# ELC102_-_Red_Digits.net
KiCad netlist of a schematic drawn in Altium Designer
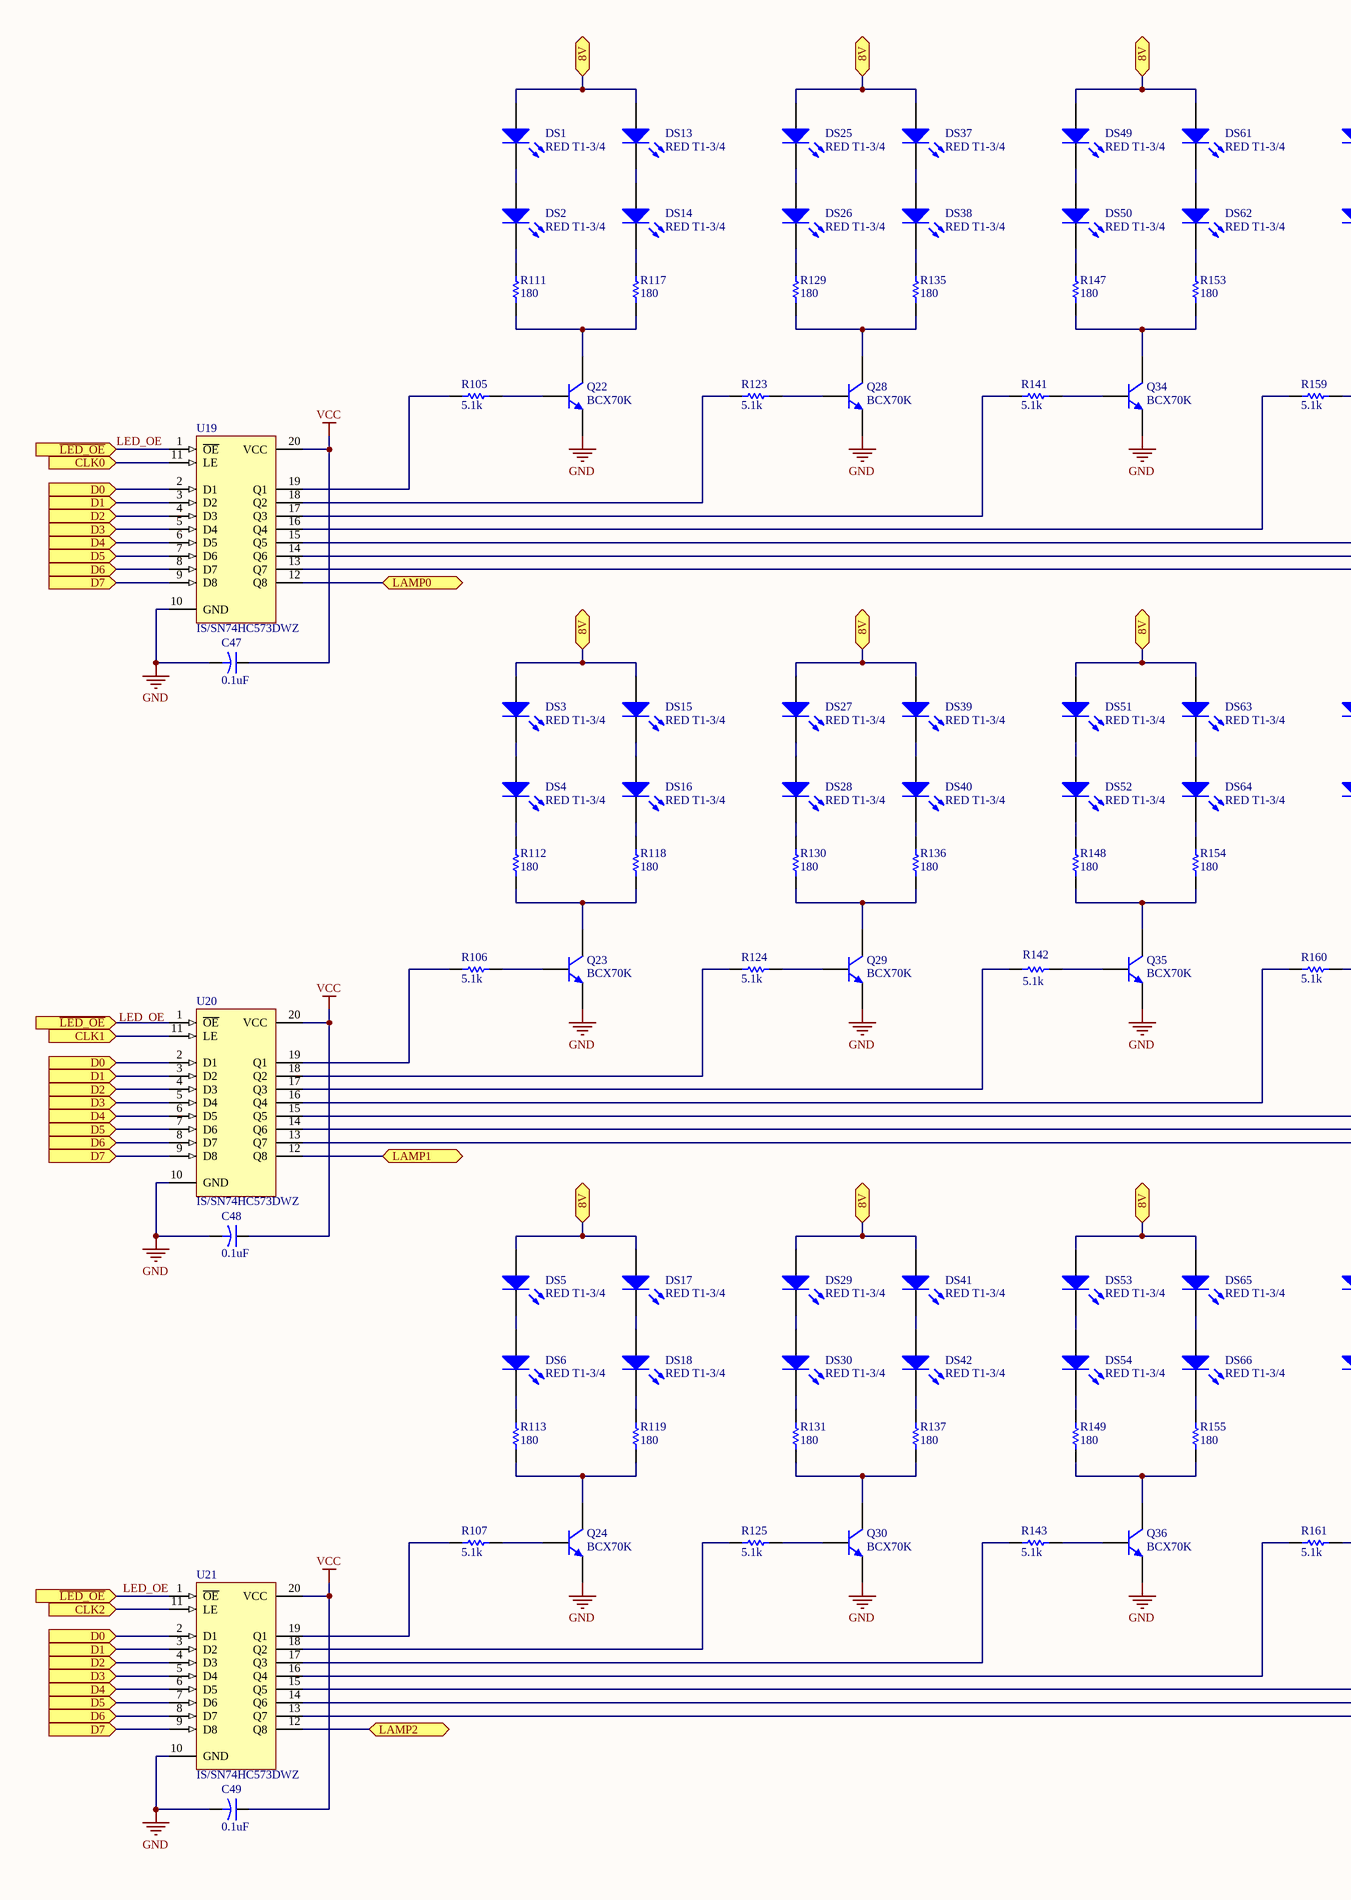
[diagram p0: ELC102 - Red Digits.SchDoc, left]
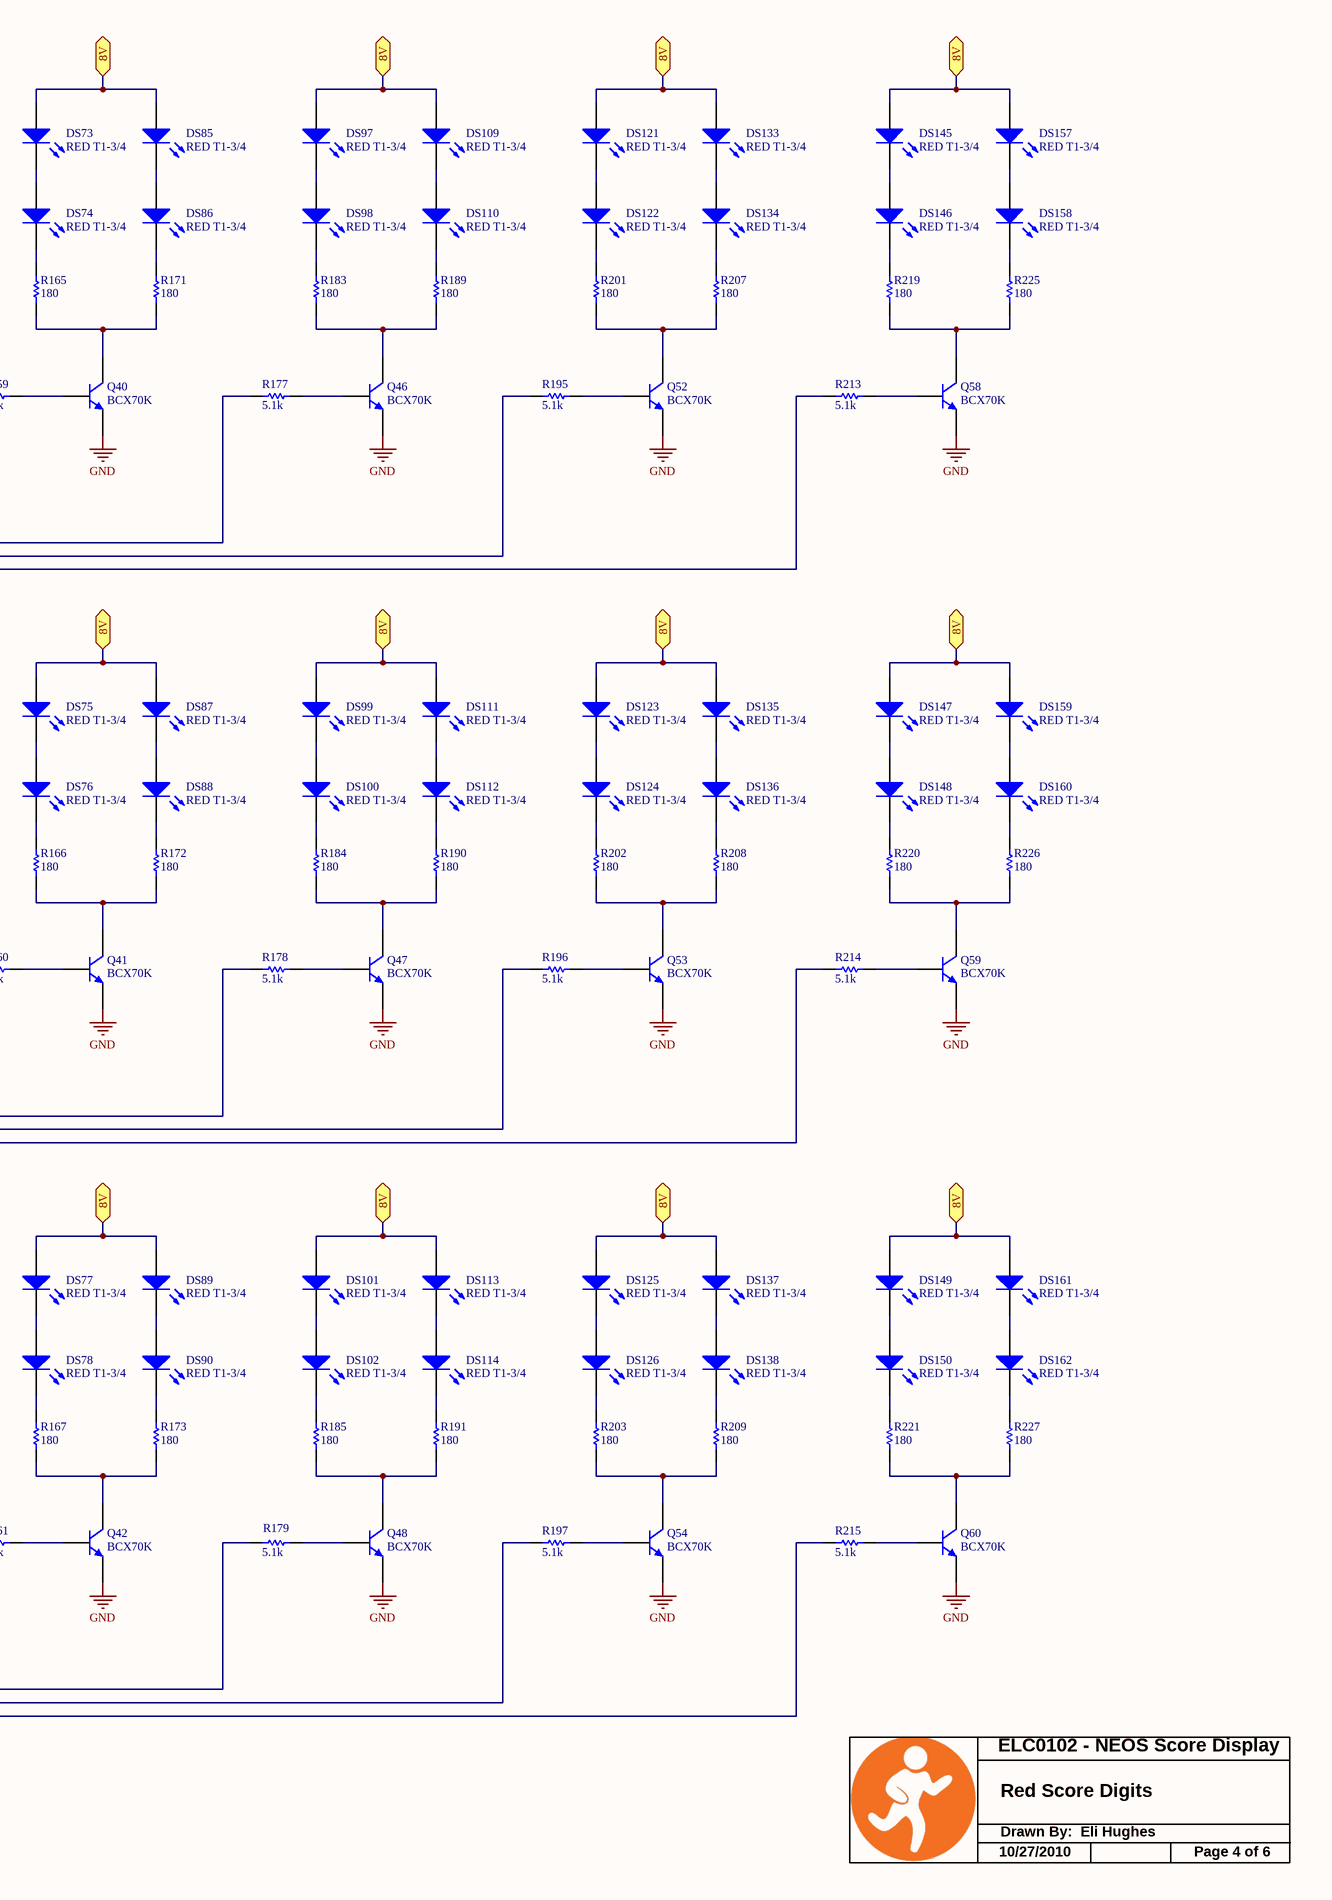
[diagram p1: ELC102 - Red Digits.SchDoc, right]

(export (version "E")
  (design (tool "Eeschema 10.0.6"))
  (components
    (comp (ref "C47")
      (value "0.1uF")
      (footprint "C0805")
      (description "CAP .10UF 50V CERAMIC X7R 0805")
      (fields
        (field (name "MANUFACTURER") "Kemet")
        (field (name "MANUFACTURER PART NUMBER") "C0805C104K5RACTU")
        (field (name "SOURCE") "Digikey")
      )
      (libsource (lib "ELC102 - Scoreboard") (part "CS/C0805C104K5RACK"))
    )
    (comp (ref "C48")
      (value "0.1uF")
      (footprint "C0805")
      (description "CAP .10UF 50V CERAMIC X7R 0805")
      (fields
        (field (name "MANUFACTURER") "Kemet")
        (field (name "MANUFACTURER PART NUMBER") "C0805C104K5RACTU")
        (field (name "SOURCE") "Digikey")
      )
      (libsource (lib "ELC102 - Scoreboard") (part "CS/C0805C104K5RACK"))
    )
    (comp (ref "C49")
      (value "0.1uF")
      (footprint "C0805")
      (description "CAP .10UF 50V CERAMIC X7R 0805")
      (fields
        (field (name "MANUFACTURER") "Kemet")
        (field (name "MANUFACTURER PART NUMBER") "C0805C104K5RACTU")
        (field (name "SOURCE") "Digikey")
      )
      (libsource (lib "ELC102 - Scoreboard") (part "CS/C0805C104K5RACK"))
    )
    (comp (ref "DS1")
      (value "RED T1-3/4")
      (footprint "LED T1-3/4 Flush")
      (description "Optek LED Red /Clear High Brightness T1-3/4")
      (fields
        (field (name "MANUFACTURER") "TT Electronics/Optek Technology")
        (field (name "MANUFACTURER PART NUMBER") "OVLFR3C7")
        (field (name "SOURCE") "Digikey")
      )
      (libsource (lib "ScoreBoard") (part "LRCOVLFR3C7Z"))
    )
    (comp (ref "DS2")
      (value "RED T1-3/4")
      (footprint "LED T1-3/4 Flush")
      (description "Optek LED Red /Clear High Brightness T1-3/4")
      (fields
        (field (name "MANUFACTURER") "TT Electronics/Optek Technology")
        (field (name "MANUFACTURER PART NUMBER") "OVLFR3C7")
        (field (name "SOURCE") "Digikey")
      )
      (libsource (lib "ScoreBoard") (part "LRCOVLFR3C7Z"))
    )
    (comp (ref "DS3")
      (value "RED T1-3/4")
      (footprint "LED T1-3/4 Flush")
      (description "Optek LED Red /Clear High Brightness T1-3/4")
      (fields
        (field (name "MANUFACTURER") "TT Electronics/Optek Technology")
        (field (name "MANUFACTURER PART NUMBER") "OVLFR3C7")
        (field (name "SOURCE") "Digikey")
      )
      (libsource (lib "ScoreBoard") (part "LRCOVLFR3C7Z"))
    )
    (comp (ref "DS4")
      (value "RED T1-3/4")
      (footprint "LED T1-3/4 Flush")
      (description "Optek LED Red /Clear High Brightness T1-3/4")
      (fields
        (field (name "MANUFACTURER") "TT Electronics/Optek Technology")
        (field (name "MANUFACTURER PART NUMBER") "OVLFR3C7")
        (field (name "SOURCE") "Digikey")
      )
      (libsource (lib "ScoreBoard") (part "LRCOVLFR3C7Z"))
    )
    (comp (ref "DS5")
      (value "RED T1-3/4")
      (footprint "LED T1-3/4 Flush")
      (description "Optek LED Red /Clear High Brightness T1-3/4")
      (fields
        (field (name "MANUFACTURER") "TT Electronics/Optek Technology")
        (field (name "MANUFACTURER PART NUMBER") "OVLFR3C7")
        (field (name "SOURCE") "Digikey")
      )
      (libsource (lib "ScoreBoard") (part "LRCOVLFR3C7Z"))
    )
    (comp (ref "DS6")
      (value "RED T1-3/4")
      (footprint "LED T1-3/4 Flush")
      (description "Optek LED Red /Clear High Brightness T1-3/4")
      (fields
        (field (name "MANUFACTURER") "TT Electronics/Optek Technology")
        (field (name "MANUFACTURER PART NUMBER") "OVLFR3C7")
        (field (name "SOURCE") "Digikey")
      )
      (libsource (lib "ScoreBoard") (part "LRCOVLFR3C7Z"))
    )
    (comp (ref "DS13")
      (value "RED T1-3/4")
      (footprint "LED T1-3/4 Flush")
      (description "Optek LED Red /Clear High Brightness T1-3/4")
      (fields
        (field (name "MANUFACTURER") "TT Electronics/Optek Technology")
        (field (name "MANUFACTURER PART NUMBER") "OVLFR3C7")
        (field (name "SOURCE") "Digikey")
      )
      (libsource (lib "ScoreBoard") (part "LRCOVLFR3C7Z"))
    )
    (comp (ref "DS14")
      (value "RED T1-3/4")
      (footprint "LED T1-3/4 Flush")
      (description "Optek LED Red /Clear High Brightness T1-3/4")
      (fields
        (field (name "MANUFACTURER") "TT Electronics/Optek Technology")
        (field (name "MANUFACTURER PART NUMBER") "OVLFR3C7")
        (field (name "SOURCE") "Digikey")
      )
      (libsource (lib "ScoreBoard") (part "LRCOVLFR3C7Z"))
    )
    (comp (ref "DS15")
      (value "RED T1-3/4")
      (footprint "LED T1-3/4 Flush")
      (description "Optek LED Red /Clear High Brightness T1-3/4")
      (fields
        (field (name "MANUFACTURER") "TT Electronics/Optek Technology")
        (field (name "MANUFACTURER PART NUMBER") "OVLFR3C7")
        (field (name "SOURCE") "Digikey")
      )
      (libsource (lib "ScoreBoard") (part "LRCOVLFR3C7Z"))
    )
    (comp (ref "DS16")
      (value "RED T1-3/4")
      (footprint "LED T1-3/4 Flush")
      (description "Optek LED Red /Clear High Brightness T1-3/4")
      (fields
        (field (name "MANUFACTURER") "TT Electronics/Optek Technology")
        (field (name "MANUFACTURER PART NUMBER") "OVLFR3C7")
        (field (name "SOURCE") "Digikey")
      )
      (libsource (lib "ScoreBoard") (part "LRCOVLFR3C7Z"))
    )
    (comp (ref "DS17")
      (value "RED T1-3/4")
      (footprint "LED T1-3/4 Flush")
      (description "Optek LED Red /Clear High Brightness T1-3/4")
      (fields
        (field (name "MANUFACTURER") "TT Electronics/Optek Technology")
        (field (name "MANUFACTURER PART NUMBER") "OVLFR3C7")
        (field (name "SOURCE") "Digikey")
      )
      (libsource (lib "ScoreBoard") (part "LRCOVLFR3C7Z"))
    )
    (comp (ref "DS18")
      (value "RED T1-3/4")
      (footprint "LED T1-3/4 Flush")
      (description "Optek LED Red /Clear High Brightness T1-3/4")
      (fields
        (field (name "MANUFACTURER") "TT Electronics/Optek Technology")
        (field (name "MANUFACTURER PART NUMBER") "OVLFR3C7")
        (field (name "SOURCE") "Digikey")
      )
      (libsource (lib "ScoreBoard") (part "LRCOVLFR3C7Z"))
    )
    (comp (ref "DS25")
      (value "RED T1-3/4")
      (footprint "LED T1-3/4 Flush")
      (description "Optek LED Red /Clear High Brightness T1-3/4")
      (fields
        (field (name "MANUFACTURER") "TT Electronics/Optek Technology")
        (field (name "MANUFACTURER PART NUMBER") "OVLFR3C7")
        (field (name "SOURCE") "Digikey")
      )
      (libsource (lib "ScoreBoard") (part "LRCOVLFR3C7Z"))
    )
    (comp (ref "DS26")
      (value "RED T1-3/4")
      (footprint "LED T1-3/4 Flush")
      (description "Optek LED Red /Clear High Brightness T1-3/4")
      (fields
        (field (name "MANUFACTURER") "TT Electronics/Optek Technology")
        (field (name "MANUFACTURER PART NUMBER") "OVLFR3C7")
        (field (name "SOURCE") "Digikey")
      )
      (libsource (lib "ScoreBoard") (part "LRCOVLFR3C7Z"))
    )
    (comp (ref "DS27")
      (value "RED T1-3/4")
      (footprint "LED T1-3/4 Flush")
      (description "Optek LED Red /Clear High Brightness T1-3/4")
      (fields
        (field (name "MANUFACTURER") "TT Electronics/Optek Technology")
        (field (name "MANUFACTURER PART NUMBER") "OVLFR3C7")
        (field (name "SOURCE") "Digikey")
      )
      (libsource (lib "ScoreBoard") (part "LRCOVLFR3C7Z"))
    )
    (comp (ref "DS28")
      (value "RED T1-3/4")
      (footprint "LED T1-3/4 Flush")
      (description "Optek LED Red /Clear High Brightness T1-3/4")
      (fields
        (field (name "MANUFACTURER") "TT Electronics/Optek Technology")
        (field (name "MANUFACTURER PART NUMBER") "OVLFR3C7")
        (field (name "SOURCE") "Digikey")
      )
      (libsource (lib "ScoreBoard") (part "LRCOVLFR3C7Z"))
    )
    (comp (ref "DS29")
      (value "RED T1-3/4")
      (footprint "LED T1-3/4 Flush")
      (description "Optek LED Red /Clear High Brightness T1-3/4")
      (fields
        (field (name "MANUFACTURER") "TT Electronics/Optek Technology")
        (field (name "MANUFACTURER PART NUMBER") "OVLFR3C7")
        (field (name "SOURCE") "Digikey")
      )
      (libsource (lib "ScoreBoard") (part "LRCOVLFR3C7Z"))
    )
    (comp (ref "DS30")
      (value "RED T1-3/4")
      (footprint "LED T1-3/4 Flush")
      (description "Optek LED Red /Clear High Brightness T1-3/4")
      (fields
        (field (name "MANUFACTURER") "TT Electronics/Optek Technology")
        (field (name "MANUFACTURER PART NUMBER") "OVLFR3C7")
        (field (name "SOURCE") "Digikey")
      )
      (libsource (lib "ScoreBoard") (part "LRCOVLFR3C7Z"))
    )
    (comp (ref "DS37")
      (value "RED T1-3/4")
      (footprint "LED T1-3/4 Flush")
      (description "Optek LED Red /Clear High Brightness T1-3/4")
      (fields
        (field (name "MANUFACTURER") "TT Electronics/Optek Technology")
        (field (name "MANUFACTURER PART NUMBER") "OVLFR3C7")
        (field (name "SOURCE") "Digikey")
      )
      (libsource (lib "ScoreBoard") (part "LRCOVLFR3C7Z"))
    )
    (comp (ref "DS38")
      (value "RED T1-3/4")
      (footprint "LED T1-3/4 Flush")
      (description "Optek LED Red /Clear High Brightness T1-3/4")
      (fields
        (field (name "MANUFACTURER") "TT Electronics/Optek Technology")
        (field (name "MANUFACTURER PART NUMBER") "OVLFR3C7")
        (field (name "SOURCE") "Digikey")
      )
      (libsource (lib "ScoreBoard") (part "LRCOVLFR3C7Z"))
    )
    (comp (ref "DS39")
      (value "RED T1-3/4")
      (footprint "LED T1-3/4 Flush")
      (description "Optek LED Red /Clear High Brightness T1-3/4")
      (fields
        (field (name "MANUFACTURER") "TT Electronics/Optek Technology")
        (field (name "MANUFACTURER PART NUMBER") "OVLFR3C7")
        (field (name "SOURCE") "Digikey")
      )
      (libsource (lib "ScoreBoard") (part "LRCOVLFR3C7Z"))
    )
    (comp (ref "DS40")
      (value "RED T1-3/4")
      (footprint "LED T1-3/4 Flush")
      (description "Optek LED Red /Clear High Brightness T1-3/4")
      (fields
        (field (name "MANUFACTURER") "TT Electronics/Optek Technology")
        (field (name "MANUFACTURER PART NUMBER") "OVLFR3C7")
        (field (name "SOURCE") "Digikey")
      )
      (libsource (lib "ScoreBoard") (part "LRCOVLFR3C7Z"))
    )
    (comp (ref "DS41")
      (value "RED T1-3/4")
      (footprint "LED T1-3/4 Flush")
      (description "Optek LED Red /Clear High Brightness T1-3/4")
      (fields
        (field (name "MANUFACTURER") "TT Electronics/Optek Technology")
        (field (name "MANUFACTURER PART NUMBER") "OVLFR3C7")
        (field (name "SOURCE") "Digikey")
      )
      (libsource (lib "ScoreBoard") (part "LRCOVLFR3C7Z"))
    )
    (comp (ref "DS42")
      (value "RED T1-3/4")
      (footprint "LED T1-3/4 Flush")
      (description "Optek LED Red /Clear High Brightness T1-3/4")
      (fields
        (field (name "MANUFACTURER") "TT Electronics/Optek Technology")
        (field (name "MANUFACTURER PART NUMBER") "OVLFR3C7")
        (field (name "SOURCE") "Digikey")
      )
      (libsource (lib "ScoreBoard") (part "LRCOVLFR3C7Z"))
    )
    (comp (ref "DS49")
      (value "RED T1-3/4")
      (footprint "LED T1-3/4 Flush")
      (description "Optek LED Red /Clear High Brightness T1-3/4")
      (fields
        (field (name "MANUFACTURER") "TT Electronics/Optek Technology")
        (field (name "MANUFACTURER PART NUMBER") "OVLFR3C7")
        (field (name "SOURCE") "Digikey")
      )
      (libsource (lib "ScoreBoard") (part "LRCOVLFR3C7Z"))
    )
    (comp (ref "DS50")
      (value "RED T1-3/4")
      (footprint "LED T1-3/4 Flush")
      (description "Optek LED Red /Clear High Brightness T1-3/4")
      (fields
        (field (name "MANUFACTURER") "TT Electronics/Optek Technology")
        (field (name "MANUFACTURER PART NUMBER") "OVLFR3C7")
        (field (name "SOURCE") "Digikey")
      )
      (libsource (lib "ScoreBoard") (part "LRCOVLFR3C7Z"))
    )
    (comp (ref "DS51")
      (value "RED T1-3/4")
      (footprint "LED T1-3/4 Flush")
      (description "Optek LED Red /Clear High Brightness T1-3/4")
      (fields
        (field (name "MANUFACTURER") "TT Electronics/Optek Technology")
        (field (name "MANUFACTURER PART NUMBER") "OVLFR3C7")
        (field (name "SOURCE") "Digikey")
      )
      (libsource (lib "ScoreBoard") (part "LRCOVLFR3C7Z"))
    )
    (comp (ref "DS52")
      (value "RED T1-3/4")
      (footprint "LED T1-3/4 Flush")
      (description "Optek LED Red /Clear High Brightness T1-3/4")
      (fields
        (field (name "MANUFACTURER") "TT Electronics/Optek Technology")
        (field (name "MANUFACTURER PART NUMBER") "OVLFR3C7")
        (field (name "SOURCE") "Digikey")
      )
      (libsource (lib "ScoreBoard") (part "LRCOVLFR3C7Z"))
    )
    (comp (ref "DS53")
      (value "RED T1-3/4")
      (footprint "LED T1-3/4 Flush")
      (description "Optek LED Red /Clear High Brightness T1-3/4")
      (fields
        (field (name "MANUFACTURER") "TT Electronics/Optek Technology")
        (field (name "MANUFACTURER PART NUMBER") "OVLFR3C7")
        (field (name "SOURCE") "Digikey")
      )
      (libsource (lib "ScoreBoard") (part "LRCOVLFR3C7Z"))
    )
    (comp (ref "DS54")
      (value "RED T1-3/4")
      (footprint "LED T1-3/4 Flush")
      (description "Optek LED Red /Clear High Brightness T1-3/4")
      (fields
        (field (name "MANUFACTURER") "TT Electronics/Optek Technology")
        (field (name "MANUFACTURER PART NUMBER") "OVLFR3C7")
        (field (name "SOURCE") "Digikey")
      )
      (libsource (lib "ScoreBoard") (part "LRCOVLFR3C7Z"))
    )
    (comp (ref "DS61")
      (value "RED T1-3/4")
      (footprint "LED T1-3/4 Flush")
      (description "Optek LED Red /Clear High Brightness T1-3/4")
      (fields
        (field (name "MANUFACTURER") "TT Electronics/Optek Technology")
        (field (name "MANUFACTURER PART NUMBER") "OVLFR3C7")
        (field (name "SOURCE") "Digikey")
      )
      (libsource (lib "ScoreBoard") (part "LRCOVLFR3C7Z"))
    )
    (comp (ref "DS62")
      (value "RED T1-3/4")
      (footprint "LED T1-3/4 Flush")
      (description "Optek LED Red /Clear High Brightness T1-3/4")
      (fields
        (field (name "MANUFACTURER") "TT Electronics/Optek Technology")
        (field (name "MANUFACTURER PART NUMBER") "OVLFR3C7")
        (field (name "SOURCE") "Digikey")
      )
      (libsource (lib "ScoreBoard") (part "LRCOVLFR3C7Z"))
    )
    (comp (ref "DS63")
      (value "RED T1-3/4")
      (footprint "LED T1-3/4 Flush")
      (description "Optek LED Red /Clear High Brightness T1-3/4")
      (fields
        (field (name "MANUFACTURER") "TT Electronics/Optek Technology")
        (field (name "MANUFACTURER PART NUMBER") "OVLFR3C7")
        (field (name "SOURCE") "Digikey")
      )
      (libsource (lib "ScoreBoard") (part "LRCOVLFR3C7Z"))
    )
    (comp (ref "DS64")
      (value "RED T1-3/4")
      (footprint "LED T1-3/4 Flush")
      (description "Optek LED Red /Clear High Brightness T1-3/4")
      (fields
        (field (name "MANUFACTURER") "TT Electronics/Optek Technology")
        (field (name "MANUFACTURER PART NUMBER") "OVLFR3C7")
        (field (name "SOURCE") "Digikey")
      )
      (libsource (lib "ScoreBoard") (part "LRCOVLFR3C7Z"))
    )
    (comp (ref "DS65")
      (value "RED T1-3/4")
      (footprint "LED T1-3/4 Flush")
      (description "Optek LED Red /Clear High Brightness T1-3/4")
      (fields
        (field (name "MANUFACTURER") "TT Electronics/Optek Technology")
        (field (name "MANUFACTURER PART NUMBER") "OVLFR3C7")
        (field (name "SOURCE") "Digikey")
      )
      (libsource (lib "ScoreBoard") (part "LRCOVLFR3C7Z"))
    )
    (comp (ref "DS66")
      (value "RED T1-3/4")
      (footprint "LED T1-3/4 Flush")
      (description "Optek LED Red /Clear High Brightness T1-3/4")
      (fields
        (field (name "MANUFACTURER") "TT Electronics/Optek Technology")
        (field (name "MANUFACTURER PART NUMBER") "OVLFR3C7")
        (field (name "SOURCE") "Digikey")
      )
      (libsource (lib "ScoreBoard") (part "LRCOVLFR3C7Z"))
    )
    (comp (ref "DS73")
      (value "RED T1-3/4")
      (footprint "LED T1-3/4 Flush")
      (description "Optek LED Red /Clear High Brightness T1-3/4")
      (fields
        (field (name "MANUFACTURER") "TT Electronics/Optek Technology")
        (field (name "MANUFACTURER PART NUMBER") "OVLFR3C7")
        (field (name "SOURCE") "Digikey")
      )
      (libsource (lib "ScoreBoard") (part "LRCOVLFR3C7Z"))
    )
    (comp (ref "DS74")
      (value "RED T1-3/4")
      (footprint "LED T1-3/4 Flush")
      (description "Optek LED Red /Clear High Brightness T1-3/4")
      (fields
        (field (name "MANUFACTURER") "TT Electronics/Optek Technology")
        (field (name "MANUFACTURER PART NUMBER") "OVLFR3C7")
        (field (name "SOURCE") "Digikey")
      )
      (libsource (lib "ScoreBoard") (part "LRCOVLFR3C7Z"))
    )
    (comp (ref "DS75")
      (value "RED T1-3/4")
      (footprint "LED T1-3/4 Flush")
      (description "Optek LED Red /Clear High Brightness T1-3/4")
      (fields
        (field (name "MANUFACTURER") "TT Electronics/Optek Technology")
        (field (name "MANUFACTURER PART NUMBER") "OVLFR3C7")
        (field (name "SOURCE") "Digikey")
      )
      (libsource (lib "ScoreBoard") (part "LRCOVLFR3C7Z"))
    )
    (comp (ref "DS76")
      (value "RED T1-3/4")
      (footprint "LED T1-3/4 Flush")
      (description "Optek LED Red /Clear High Brightness T1-3/4")
      (fields
        (field (name "MANUFACTURER") "TT Electronics/Optek Technology")
        (field (name "MANUFACTURER PART NUMBER") "OVLFR3C7")
        (field (name "SOURCE") "Digikey")
      )
      (libsource (lib "ScoreBoard") (part "LRCOVLFR3C7Z"))
    )
    (comp (ref "DS77")
      (value "RED T1-3/4")
      (footprint "LED T1-3/4 Flush")
      (description "Optek LED Red /Clear High Brightness T1-3/4")
      (fields
        (field (name "MANUFACTURER") "TT Electronics/Optek Technology")
        (field (name "MANUFACTURER PART NUMBER") "OVLFR3C7")
        (field (name "SOURCE") "Digikey")
      )
      (libsource (lib "ScoreBoard") (part "LRCOVLFR3C7Z"))
    )
    (comp (ref "DS78")
      (value "RED T1-3/4")
      (footprint "LED T1-3/4 Flush")
      (description "Optek LED Red /Clear High Brightness T1-3/4")
      (fields
        (field (name "MANUFACTURER") "TT Electronics/Optek Technology")
        (field (name "MANUFACTURER PART NUMBER") "OVLFR3C7")
        (field (name "SOURCE") "Digikey")
      )
      (libsource (lib "ScoreBoard") (part "LRCOVLFR3C7Z"))
    )
    (comp (ref "DS85")
      (value "RED T1-3/4")
      (footprint "LED T1-3/4 Flush")
      (description "Optek LED Red /Clear High Brightness T1-3/4")
      (fields
        (field (name "MANUFACTURER") "TT Electronics/Optek Technology")
        (field (name "MANUFACTURER PART NUMBER") "OVLFR3C7")
        (field (name "SOURCE") "Digikey")
      )
      (libsource (lib "ScoreBoard") (part "LRCOVLFR3C7Z"))
    )
    (comp (ref "DS86")
      (value "RED T1-3/4")
      (footprint "LED T1-3/4 Flush")
      (description "Optek LED Red /Clear High Brightness T1-3/4")
      (fields
        (field (name "MANUFACTURER") "TT Electronics/Optek Technology")
        (field (name "MANUFACTURER PART NUMBER") "OVLFR3C7")
        (field (name "SOURCE") "Digikey")
      )
      (libsource (lib "ScoreBoard") (part "LRCOVLFR3C7Z"))
    )
    (comp (ref "DS87")
      (value "RED T1-3/4")
      (footprint "LED T1-3/4 Flush")
      (description "Optek LED Red /Clear High Brightness T1-3/4")
      (fields
        (field (name "MANUFACTURER") "TT Electronics/Optek Technology")
        (field (name "MANUFACTURER PART NUMBER") "OVLFR3C7")
        (field (name "SOURCE") "Digikey")
      )
      (libsource (lib "ScoreBoard") (part "LRCOVLFR3C7Z"))
    )
    (comp (ref "DS88")
      (value "RED T1-3/4")
      (footprint "LED T1-3/4 Flush")
      (description "Optek LED Red /Clear High Brightness T1-3/4")
      (fields
        (field (name "MANUFACTURER") "TT Electronics/Optek Technology")
        (field (name "MANUFACTURER PART NUMBER") "OVLFR3C7")
        (field (name "SOURCE") "Digikey")
      )
      (libsource (lib "ScoreBoard") (part "LRCOVLFR3C7Z"))
    )
    (comp (ref "DS89")
      (value "RED T1-3/4")
      (footprint "LED T1-3/4 Flush")
      (description "Optek LED Red /Clear High Brightness T1-3/4")
      (fields
        (field (name "MANUFACTURER") "TT Electronics/Optek Technology")
        (field (name "MANUFACTURER PART NUMBER") "OVLFR3C7")
        (field (name "SOURCE") "Digikey")
      )
      (libsource (lib "ScoreBoard") (part "LRCOVLFR3C7Z"))
    )
    (comp (ref "DS90")
      (value "RED T1-3/4")
      (footprint "LED T1-3/4 Flush")
      (description "Optek LED Red /Clear High Brightness T1-3/4")
      (fields
        (field (name "MANUFACTURER") "TT Electronics/Optek Technology")
        (field (name "MANUFACTURER PART NUMBER") "OVLFR3C7")
        (field (name "SOURCE") "Digikey")
      )
      (libsource (lib "ScoreBoard") (part "LRCOVLFR3C7Z"))
    )
    (comp (ref "DS97")
      (value "RED T1-3/4")
      (footprint "LED T1-3/4 Flush")
      (description "Optek LED Red /Clear High Brightness T1-3/4")
      (fields
        (field (name "MANUFACTURER") "TT Electronics/Optek Technology")
        (field (name "MANUFACTURER PART NUMBER") "OVLFR3C7")
        (field (name "SOURCE") "Digikey")
      )
      (libsource (lib "ScoreBoard") (part "LRCOVLFR3C7Z"))
    )
    (comp (ref "DS98")
      (value "RED T1-3/4")
      (footprint "LED T1-3/4 Flush")
      (description "Optek LED Red /Clear High Brightness T1-3/4")
      (fields
        (field (name "MANUFACTURER") "TT Electronics/Optek Technology")
        (field (name "MANUFACTURER PART NUMBER") "OVLFR3C7")
        (field (name "SOURCE") "Digikey")
      )
      (libsource (lib "ScoreBoard") (part "LRCOVLFR3C7Z"))
    )
    (comp (ref "DS99")
      (value "RED T1-3/4")
      (footprint "LED T1-3/4 Flush")
      (description "Optek LED Red /Clear High Brightness T1-3/4")
      (fields
        (field (name "MANUFACTURER") "TT Electronics/Optek Technology")
        (field (name "MANUFACTURER PART NUMBER") "OVLFR3C7")
        (field (name "SOURCE") "Digikey")
      )
      (libsource (lib "ScoreBoard") (part "LRCOVLFR3C7Z"))
    )
    (comp (ref "DS100")
      (value "RED T1-3/4")
      (footprint "LED T1-3/4 Flush")
      (description "Optek LED Red /Clear High Brightness T1-3/4")
      (fields
        (field (name "MANUFACTURER") "TT Electronics/Optek Technology")
        (field (name "MANUFACTURER PART NUMBER") "OVLFR3C7")
        (field (name "SOURCE") "Digikey")
      )
      (libsource (lib "ScoreBoard") (part "LRCOVLFR3C7Z"))
    )
    (comp (ref "DS101")
      (value "RED T1-3/4")
      (footprint "LED T1-3/4 Flush")
      (description "Optek LED Red /Clear High Brightness T1-3/4")
      (fields
        (field (name "MANUFACTURER") "TT Electronics/Optek Technology")
        (field (name "MANUFACTURER PART NUMBER") "OVLFR3C7")
        (field (name "SOURCE") "Digikey")
      )
      (libsource (lib "ScoreBoard") (part "LRCOVLFR3C7Z"))
    )
    (comp (ref "DS102")
      (value "RED T1-3/4")
      (footprint "LED T1-3/4 Flush")
      (description "Optek LED Red /Clear High Brightness T1-3/4")
      (fields
        (field (name "MANUFACTURER") "TT Electronics/Optek Technology")
        (field (name "MANUFACTURER PART NUMBER") "OVLFR3C7")
        (field (name "SOURCE") "Digikey")
      )
      (libsource (lib "ScoreBoard") (part "LRCOVLFR3C7Z"))
    )
    (comp (ref "DS109")
      (value "RED T1-3/4")
      (footprint "LED T1-3/4 Flush")
      (description "Optek LED Red /Clear High Brightness T1-3/4")
      (fields
        (field (name "MANUFACTURER") "TT Electronics/Optek Technology")
        (field (name "MANUFACTURER PART NUMBER") "OVLFR3C7")
        (field (name "SOURCE") "Digikey")
      )
      (libsource (lib "ScoreBoard") (part "LRCOVLFR3C7Z"))
    )
    (comp (ref "DS110")
      (value "RED T1-3/4")
      (footprint "LED T1-3/4 Flush")
      (description "Optek LED Red /Clear High Brightness T1-3/4")
      (fields
        (field (name "MANUFACTURER") "TT Electronics/Optek Technology")
        (field (name "MANUFACTURER PART NUMBER") "OVLFR3C7")
        (field (name "SOURCE") "Digikey")
      )
      (libsource (lib "ScoreBoard") (part "LRCOVLFR3C7Z"))
    )
    (comp (ref "DS111")
      (value "RED T1-3/4")
      (footprint "LED T1-3/4 Flush")
      (description "Optek LED Red /Clear High Brightness T1-3/4")
      (fields
        (field (name "MANUFACTURER") "TT Electronics/Optek Technology")
        (field (name "MANUFACTURER PART NUMBER") "OVLFR3C7")
        (field (name "SOURCE") "Digikey")
      )
      (libsource (lib "ScoreBoard") (part "LRCOVLFR3C7Z"))
    )
    (comp (ref "DS112")
      (value "RED T1-3/4")
      (footprint "LED T1-3/4 Flush")
      (description "Optek LED Red /Clear High Brightness T1-3/4")
      (fields
        (field (name "MANUFACTURER") "TT Electronics/Optek Technology")
        (field (name "MANUFACTURER PART NUMBER") "OVLFR3C7")
        (field (name "SOURCE") "Digikey")
      )
      (libsource (lib "ScoreBoard") (part "LRCOVLFR3C7Z"))
    )
    (comp (ref "DS113")
      (value "RED T1-3/4")
      (footprint "LED T1-3/4 Flush")
      (description "Optek LED Red /Clear High Brightness T1-3/4")
      (fields
        (field (name "MANUFACTURER") "TT Electronics/Optek Technology")
        (field (name "MANUFACTURER PART NUMBER") "OVLFR3C7")
        (field (name "SOURCE") "Digikey")
      )
      (libsource (lib "ScoreBoard") (part "LRCOVLFR3C7Z"))
    )
    (comp (ref "DS114")
      (value "RED T1-3/4")
      (footprint "LED T1-3/4 Flush")
      (description "Optek LED Red /Clear High Brightness T1-3/4")
      (fields
        (field (name "MANUFACTURER") "TT Electronics/Optek Technology")
        (field (name "MANUFACTURER PART NUMBER") "OVLFR3C7")
        (field (name "SOURCE") "Digikey")
      )
      (libsource (lib "ScoreBoard") (part "LRCOVLFR3C7Z"))
    )
    (comp (ref "DS121")
      (value "RED T1-3/4")
      (footprint "LED T1-3/4 Flush")
      (description "Optek LED Red /Clear High Brightness T1-3/4")
      (fields
        (field (name "MANUFACTURER") "TT Electronics/Optek Technology")
        (field (name "MANUFACTURER PART NUMBER") "OVLFR3C7")
        (field (name "SOURCE") "Digikey")
      )
      (libsource (lib "ScoreBoard") (part "LRCOVLFR3C7Z"))
    )
    (comp (ref "DS122")
      (value "RED T1-3/4")
      (footprint "LED T1-3/4 Flush")
      (description "Optek LED Red /Clear High Brightness T1-3/4")
      (fields
        (field (name "MANUFACTURER") "TT Electronics/Optek Technology")
        (field (name "MANUFACTURER PART NUMBER") "OVLFR3C7")
        (field (name "SOURCE") "Digikey")
      )
      (libsource (lib "ScoreBoard") (part "LRCOVLFR3C7Z"))
    )
    (comp (ref "DS123")
      (value "RED T1-3/4")
      (footprint "LED T1-3/4 Flush")
      (description "Optek LED Red /Clear High Brightness T1-3/4")
      (fields
        (field (name "MANUFACTURER") "TT Electronics/Optek Technology")
        (field (name "MANUFACTURER PART NUMBER") "OVLFR3C7")
        (field (name "SOURCE") "Digikey")
      )
      (libsource (lib "ScoreBoard") (part "LRCOVLFR3C7Z"))
    )
    (comp (ref "DS124")
      (value "RED T1-3/4")
      (footprint "LED T1-3/4 Flush")
      (description "Optek LED Red /Clear High Brightness T1-3/4")
      (fields
        (field (name "MANUFACTURER") "TT Electronics/Optek Technology")
        (field (name "MANUFACTURER PART NUMBER") "OVLFR3C7")
        (field (name "SOURCE") "Digikey")
      )
      (libsource (lib "ScoreBoard") (part "LRCOVLFR3C7Z"))
    )
    (comp (ref "DS125")
      (value "RED T1-3/4")
      (footprint "LED T1-3/4 Flush")
      (description "Optek LED Red /Clear High Brightness T1-3/4")
      (fields
        (field (name "MANUFACTURER") "TT Electronics/Optek Technology")
        (field (name "MANUFACTURER PART NUMBER") "OVLFR3C7")
        (field (name "SOURCE") "Digikey")
      )
      (libsource (lib "ScoreBoard") (part "LRCOVLFR3C7Z"))
    )
    (comp (ref "DS126")
      (value "RED T1-3/4")
      (footprint "LED T1-3/4 Flush")
      (description "Optek LED Red /Clear High Brightness T1-3/4")
      (fields
        (field (name "MANUFACTURER") "TT Electronics/Optek Technology")
        (field (name "MANUFACTURER PART NUMBER") "OVLFR3C7")
        (field (name "SOURCE") "Digikey")
      )
      (libsource (lib "ScoreBoard") (part "LRCOVLFR3C7Z"))
    )
    (comp (ref "DS133")
      (value "RED T1-3/4")
      (footprint "LED T1-3/4 Flush")
      (description "Optek LED Red /Clear High Brightness T1-3/4")
      (fields
        (field (name "MANUFACTURER") "TT Electronics/Optek Technology")
        (field (name "MANUFACTURER PART NUMBER") "OVLFR3C7")
        (field (name "SOURCE") "Digikey")
      )
      (libsource (lib "ScoreBoard") (part "LRCOVLFR3C7Z"))
    )
    (comp (ref "DS134")
      (value "RED T1-3/4")
      (footprint "LED T1-3/4 Flush")
      (description "Optek LED Red /Clear High Brightness T1-3/4")
      (fields
        (field (name "MANUFACTURER") "TT Electronics/Optek Technology")
        (field (name "MANUFACTURER PART NUMBER") "OVLFR3C7")
        (field (name "SOURCE") "Digikey")
      )
      (libsource (lib "ScoreBoard") (part "LRCOVLFR3C7Z"))
    )
    (comp (ref "DS135")
      (value "RED T1-3/4")
      (footprint "LED T1-3/4 Flush")
      (description "Optek LED Red /Clear High Brightness T1-3/4")
      (fields
        (field (name "MANUFACTURER") "TT Electronics/Optek Technology")
        (field (name "MANUFACTURER PART NUMBER") "OVLFR3C7")
        (field (name "SOURCE") "Digikey")
      )
      (libsource (lib "ScoreBoard") (part "LRCOVLFR3C7Z"))
    )
    (comp (ref "DS136")
      (value "RED T1-3/4")
      (footprint "LED T1-3/4 Flush")
      (description "Optek LED Red /Clear High Brightness T1-3/4")
      (fields
        (field (name "MANUFACTURER") "TT Electronics/Optek Technology")
        (field (name "MANUFACTURER PART NUMBER") "OVLFR3C7")
        (field (name "SOURCE") "Digikey")
      )
      (libsource (lib "ScoreBoard") (part "LRCOVLFR3C7Z"))
    )
    (comp (ref "DS137")
      (value "RED T1-3/4")
      (footprint "LED T1-3/4 Flush")
      (description "Optek LED Red /Clear High Brightness T1-3/4")
      (fields
        (field (name "MANUFACTURER") "TT Electronics/Optek Technology")
        (field (name "MANUFACTURER PART NUMBER") "OVLFR3C7")
        (field (name "SOURCE") "Digikey")
      )
      (libsource (lib "ScoreBoard") (part "LRCOVLFR3C7Z"))
    )
    (comp (ref "DS138")
      (value "RED T1-3/4")
      (footprint "LED T1-3/4 Flush")
      (description "Optek LED Red /Clear High Brightness T1-3/4")
      (fields
        (field (name "MANUFACTURER") "TT Electronics/Optek Technology")
        (field (name "MANUFACTURER PART NUMBER") "OVLFR3C7")
        (field (name "SOURCE") "Digikey")
      )
      (libsource (lib "ScoreBoard") (part "LRCOVLFR3C7Z"))
    )
    (comp (ref "DS145")
      (value "RED T1-3/4")
      (footprint "LED T1-3/4 Flush")
      (description "Optek LED Red /Clear High Brightness T1-3/4")
      (fields
        (field (name "MANUFACTURER") "TT Electronics/Optek Technology")
        (field (name "MANUFACTURER PART NUMBER") "OVLFR3C7")
        (field (name "SOURCE") "Digikey")
      )
      (libsource (lib "ScoreBoard") (part "LRCOVLFR3C7Z"))
    )
    (comp (ref "DS146")
      (value "RED T1-3/4")
      (footprint "LED T1-3/4 Flush")
      (description "Optek LED Red /Clear High Brightness T1-3/4")
      (fields
        (field (name "MANUFACTURER") "TT Electronics/Optek Technology")
        (field (name "MANUFACTURER PART NUMBER") "OVLFR3C7")
        (field (name "SOURCE") "Digikey")
      )
      (libsource (lib "ScoreBoard") (part "LRCOVLFR3C7Z"))
    )
    (comp (ref "DS147")
      (value "RED T1-3/4")
      (footprint "LED T1-3/4 Flush")
      (description "Optek LED Red /Clear High Brightness T1-3/4")
      (fields
        (field (name "MANUFACTURER") "TT Electronics/Optek Technology")
        (field (name "MANUFACTURER PART NUMBER") "OVLFR3C7")
        (field (name "SOURCE") "Digikey")
      )
      (libsource (lib "ScoreBoard") (part "LRCOVLFR3C7Z"))
    )
    (comp (ref "DS148")
      (value "RED T1-3/4")
      (footprint "LED T1-3/4 Flush")
      (description "Optek LED Red /Clear High Brightness T1-3/4")
      (fields
        (field (name "MANUFACTURER") "TT Electronics/Optek Technology")
        (field (name "MANUFACTURER PART NUMBER") "OVLFR3C7")
        (field (name "SOURCE") "Digikey")
      )
      (libsource (lib "ScoreBoard") (part "LRCOVLFR3C7Z"))
    )
    (comp (ref "DS149")
      (value "RED T1-3/4")
      (footprint "LED T1-3/4 Flush")
      (description "Optek LED Red /Clear High Brightness T1-3/4")
      (fields
        (field (name "MANUFACTURER") "TT Electronics/Optek Technology")
        (field (name "MANUFACTURER PART NUMBER") "OVLFR3C7")
        (field (name "SOURCE") "Digikey")
      )
      (libsource (lib "ScoreBoard") (part "LRCOVLFR3C7Z"))
    )
    (comp (ref "DS150")
      (value "RED T1-3/4")
      (footprint "LED T1-3/4 Flush")
      (description "Optek LED Red /Clear High Brightness T1-3/4")
      (fields
        (field (name "MANUFACTURER") "TT Electronics/Optek Technology")
        (field (name "MANUFACTURER PART NUMBER") "OVLFR3C7")
        (field (name "SOURCE") "Digikey")
      )
      (libsource (lib "ScoreBoard") (part "LRCOVLFR3C7Z"))
    )
    (comp (ref "DS157")
      (value "RED T1-3/4")
      (footprint "LED T1-3/4 Flush")
      (description "Optek LED Red /Clear High Brightness T1-3/4")
      (fields
        (field (name "MANUFACTURER") "TT Electronics/Optek Technology")
        (field (name "MANUFACTURER PART NUMBER") "OVLFR3C7")
        (field (name "SOURCE") "Digikey")
      )
      (libsource (lib "ScoreBoard") (part "LRCOVLFR3C7Z"))
    )
    (comp (ref "DS158")
      (value "RED T1-3/4")
      (footprint "LED T1-3/4 Flush")
      (description "Optek LED Red /Clear High Brightness T1-3/4")
      (fields
        (field (name "MANUFACTURER") "TT Electronics/Optek Technology")
        (field (name "MANUFACTURER PART NUMBER") "OVLFR3C7")
        (field (name "SOURCE") "Digikey")
      )
      (libsource (lib "ScoreBoard") (part "LRCOVLFR3C7Z"))
    )
    (comp (ref "DS159")
      (value "RED T1-3/4")
      (footprint "LED T1-3/4 Flush")
      (description "Optek LED Red /Clear High Brightness T1-3/4")
      (fields
        (field (name "MANUFACTURER") "TT Electronics/Optek Technology")
        (field (name "MANUFACTURER PART NUMBER") "OVLFR3C7")
        (field (name "SOURCE") "Digikey")
      )
      (libsource (lib "ScoreBoard") (part "LRCOVLFR3C7Z"))
    )
    (comp (ref "DS160")
      (value "RED T1-3/4")
      (footprint "LED T1-3/4 Flush")
      (description "Optek LED Red /Clear High Brightness T1-3/4")
      (fields
        (field (name "MANUFACTURER") "TT Electronics/Optek Technology")
        (field (name "MANUFACTURER PART NUMBER") "OVLFR3C7")
        (field (name "SOURCE") "Digikey")
      )
      (libsource (lib "ScoreBoard") (part "LRCOVLFR3C7Z"))
    )
    (comp (ref "DS161")
      (value "RED T1-3/4")
      (footprint "LED T1-3/4 Flush")
      (description "Optek LED Red /Clear High Brightness T1-3/4")
      (fields
        (field (name "MANUFACTURER") "TT Electronics/Optek Technology")
        (field (name "MANUFACTURER PART NUMBER") "OVLFR3C7")
        (field (name "SOURCE") "Digikey")
      )
      (libsource (lib "ScoreBoard") (part "LRCOVLFR3C7Z"))
    )
    (comp (ref "DS162")
      (value "RED T1-3/4")
      (footprint "LED T1-3/4 Flush")
      (description "Optek LED Red /Clear High Brightness T1-3/4")
      (fields
        (field (name "MANUFACTURER") "TT Electronics/Optek Technology")
        (field (name "MANUFACTURER PART NUMBER") "OVLFR3C7")
        (field (name "SOURCE") "Digikey")
      )
      (libsource (lib "ScoreBoard") (part "LRCOVLFR3C7Z"))
    )
    (comp (ref "Q22")
      (value "BCX70K")
      (footprint "SOT23")
      (description "TRANS NPN AF 45V SOT-23")
      (fields (field (name "MANUFACTURER") "Fairchild Semiconductor") (field (name "SOURCE") "Digikey"))
      (libsource (lib "ScoreBoard") (part "QS/BCX70K00Z"))
    )
    (comp (ref "Q23")
      (value "BCX70K")
      (footprint "SOT23")
      (description "TRANS NPN AF 45V SOT-23")
      (fields (field (name "MANUFACTURER") "Fairchild Semiconductor") (field (name "SOURCE") "Digikey"))
      (libsource (lib "ScoreBoard") (part "QS/BCX70K00Z"))
    )
    (comp (ref "Q24")
      (value "BCX70K")
      (footprint "SOT23")
      (description "TRANS NPN AF 45V SOT-23")
      (fields (field (name "MANUFACTURER") "Fairchild Semiconductor") (field (name "SOURCE") "Digikey"))
      (libsource (lib "ScoreBoard") (part "QS/BCX70K00Z"))
    )
    (comp (ref "Q28")
      (value "BCX70K")
      (footprint "SOT23")
      (description "TRANS NPN AF 45V SOT-23")
      (fields (field (name "MANUFACTURER") "Fairchild Semiconductor") (field (name "SOURCE") "Digikey"))
      (libsource (lib "ScoreBoard") (part "QS/BCX70K00Z"))
    )
    (comp (ref "Q29")
      (value "BCX70K")
      (footprint "SOT23")
      (description "TRANS NPN AF 45V SOT-23")
      (fields (field (name "MANUFACTURER") "Fairchild Semiconductor") (field (name "SOURCE") "Digikey"))
      (libsource (lib "ScoreBoard") (part "QS/BCX70K00Z"))
    )
    (comp (ref "Q30")
      (value "BCX70K")
      (footprint "SOT23")
      (description "TRANS NPN AF 45V SOT-23")
      (fields (field (name "MANUFACTURER") "Fairchild Semiconductor") (field (name "SOURCE") "Digikey"))
      (libsource (lib "ScoreBoard") (part "QS/BCX70K00Z"))
    )
    (comp (ref "Q34")
      (value "BCX70K")
      (footprint "SOT23")
      (description "TRANS NPN AF 45V SOT-23")
      (fields (field (name "MANUFACTURER") "Fairchild Semiconductor") (field (name "SOURCE") "Digikey"))
      (libsource (lib "ScoreBoard") (part "QS/BCX70K00Z"))
    )
    (comp (ref "Q35")
      (value "BCX70K")
      (footprint "SOT23")
      (description "TRANS NPN AF 45V SOT-23")
      (fields (field (name "MANUFACTURER") "Fairchild Semiconductor") (field (name "SOURCE") "Digikey"))
      (libsource (lib "ScoreBoard") (part "QS/BCX70K00Z"))
    )
    (comp (ref "Q36")
      (value "BCX70K")
      (footprint "SOT23")
      (description "TRANS NPN AF 45V SOT-23")
      (fields (field (name "MANUFACTURER") "Fairchild Semiconductor") (field (name "SOURCE") "Digikey"))
      (libsource (lib "ScoreBoard") (part "QS/BCX70K00Z"))
    )
    (comp (ref "Q40")
      (value "BCX70K")
      (footprint "SOT23")
      (description "TRANS NPN AF 45V SOT-23")
      (fields (field (name "MANUFACTURER") "Fairchild Semiconductor") (field (name "SOURCE") "Digikey"))
      (libsource (lib "ScoreBoard") (part "QS/BCX70K00Z"))
    )
    (comp (ref "Q41")
      (value "BCX70K")
      (footprint "SOT23")
      (description "TRANS NPN AF 45V SOT-23")
      (fields (field (name "MANUFACTURER") "Fairchild Semiconductor") (field (name "SOURCE") "Digikey"))
      (libsource (lib "ScoreBoard") (part "QS/BCX70K00Z"))
    )
    (comp (ref "Q42")
      (value "BCX70K")
      (footprint "SOT23")
      (description "TRANS NPN AF 45V SOT-23")
      (fields (field (name "MANUFACTURER") "Fairchild Semiconductor") (field (name "SOURCE") "Digikey"))
      (libsource (lib "ScoreBoard") (part "QS/BCX70K00Z"))
    )
    (comp (ref "Q46")
      (value "BCX70K")
      (footprint "SOT23")
      (description "TRANS NPN AF 45V SOT-23")
      (fields (field (name "MANUFACTURER") "Fairchild Semiconductor") (field (name "SOURCE") "Digikey"))
      (libsource (lib "ScoreBoard") (part "QS/BCX70K00Z"))
    )
    (comp (ref "Q47")
      (value "BCX70K")
      (footprint "SOT23")
      (description "TRANS NPN AF 45V SOT-23")
      (fields (field (name "MANUFACTURER") "Fairchild Semiconductor") (field (name "SOURCE") "Digikey"))
      (libsource (lib "ScoreBoard") (part "QS/BCX70K00Z"))
    )
    (comp (ref "Q48")
      (value "BCX70K")
      (footprint "SOT23")
      (description "TRANS NPN AF 45V SOT-23")
      (fields (field (name "MANUFACTURER") "Fairchild Semiconductor") (field (name "SOURCE") "Digikey"))
      (libsource (lib "ScoreBoard") (part "QS/BCX70K00Z"))
    )
    (comp (ref "Q52")
      (value "BCX70K")
      (footprint "SOT23")
      (description "TRANS NPN AF 45V SOT-23")
      (fields (field (name "MANUFACTURER") "Fairchild Semiconductor") (field (name "SOURCE") "Digikey"))
      (libsource (lib "ScoreBoard") (part "QS/BCX70K00Z"))
    )
    (comp (ref "Q53")
      (value "BCX70K")
      (footprint "SOT23")
      (description "TRANS NPN AF 45V SOT-23")
      (fields (field (name "MANUFACTURER") "Fairchild Semiconductor") (field (name "SOURCE") "Digikey"))
      (libsource (lib "ScoreBoard") (part "QS/BCX70K00Z"))
    )
    (comp (ref "Q54")
      (value "BCX70K")
      (footprint "SOT23")
      (description "TRANS NPN AF 45V SOT-23")
      (fields (field (name "MANUFACTURER") "Fairchild Semiconductor") (field (name "SOURCE") "Digikey"))
      (libsource (lib "ScoreBoard") (part "QS/BCX70K00Z"))
    )
    (comp (ref "Q58")
      (value "BCX70K")
      (footprint "SOT23")
      (description "TRANS NPN AF 45V SOT-23")
      (fields (field (name "MANUFACTURER") "Fairchild Semiconductor") (field (name "SOURCE") "Digikey"))
      (libsource (lib "ScoreBoard") (part "QS/BCX70K00Z"))
    )
    (comp (ref "Q59")
      (value "BCX70K")
      (footprint "SOT23")
      (description "TRANS NPN AF 45V SOT-23")
      (fields (field (name "MANUFACTURER") "Fairchild Semiconductor") (field (name "SOURCE") "Digikey"))
      (libsource (lib "ScoreBoard") (part "QS/BCX70K00Z"))
    )
    (comp (ref "Q60")
      (value "BCX70K")
      (footprint "SOT23")
      (description "TRANS NPN AF 45V SOT-23")
      (fields (field (name "MANUFACTURER") "Fairchild Semiconductor") (field (name "SOURCE") "Digikey"))
      (libsource (lib "ScoreBoard") (part "QS/BCX70K00Z"))
    )
    (comp (ref "R105")
      (value "5.1k")
      (footprint "R0805")
      (description "RES 5.10K OHM 1/8W 1% 0805 SMD")
      (fields
        (field (name "MANUFACTURER") "Panasonic - ECG")
        (field (name "MANUFACTURER PART NUMBER") "ERJ-6ENF5101V")
      )
      (libsource (lib "eRCL") (part "ERJ-6ENF5101V"))
    )
    (comp (ref "R106")
      (value "5.1k")
      (footprint "R0805")
      (description "RES 5.10K OHM 1/8W 1% 0805 SMD")
      (fields
        (field (name "MANUFACTURER") "Panasonic - ECG")
        (field (name "MANUFACTURER PART NUMBER") "ERJ-6ENF5101V")
      )
      (libsource (lib "eRCL") (part "ERJ-6ENF5101V"))
    )
    (comp (ref "R107")
      (value "5.1k")
      (footprint "R0805")
      (description "RES 5.10K OHM 1/8W 1% 0805 SMD")
      (fields
        (field (name "MANUFACTURER") "Panasonic - ECG")
        (field (name "MANUFACTURER PART NUMBER") "ERJ-6ENF5101V")
      )
      (libsource (lib "eRCL") (part "ERJ-6ENF5101V"))
    )
    (comp (ref "R111")
      (value "180")
      (footprint "R1206")
      (description "RES 180 OHM 1/4W 1% 1206 SMD")
      (fields
        (field (name "MANUFACTURER") "Panasonic - ECG")
        (field (name "MANUFACTURER PART NUMBER") "ERJ-8ENF1800V")
      )
      (libsource (lib "eRCL") (part "ERJ-8ENF1800V"))
    )
    (comp (ref "R112")
      (value "180")
      (footprint "R1206")
      (description "RES 180 OHM 1/4W 1% 1206 SMD")
      (fields
        (field (name "MANUFACTURER") "Panasonic - ECG")
        (field (name "MANUFACTURER PART NUMBER") "ERJ-8ENF1800V")
      )
      (libsource (lib "eRCL") (part "ERJ-8ENF1800V"))
    )
    (comp (ref "R113")
      (value "180")
      (footprint "R1206")
      (description "RES 180 OHM 1/4W 1% 1206 SMD")
      (fields
        (field (name "MANUFACTURER") "Panasonic - ECG")
        (field (name "MANUFACTURER PART NUMBER") "ERJ-8ENF1800V")
      )
      (libsource (lib "eRCL") (part "ERJ-8ENF1800V"))
    )
    (comp (ref "R117")
      (value "180")
      (footprint "R1206")
      (description "RES 180 OHM 1/4W 1% 1206 SMD")
      (fields
        (field (name "MANUFACTURER") "Panasonic - ECG")
        (field (name "MANUFACTURER PART NUMBER") "ERJ-8ENF1800V")
      )
      (libsource (lib "eRCL") (part "ERJ-8ENF1800V"))
    )
    (comp (ref "R118")
      (value "180")
      (footprint "R1206")
      (description "RES 180 OHM 1/4W 1% 1206 SMD")
      (fields
        (field (name "MANUFACTURER") "Panasonic - ECG")
        (field (name "MANUFACTURER PART NUMBER") "ERJ-8ENF1800V")
      )
      (libsource (lib "eRCL") (part "ERJ-8ENF1800V"))
    )
    (comp (ref "R119")
      (value "180")
      (footprint "R1206")
      (description "RES 180 OHM 1/4W 1% 1206 SMD")
      (fields
        (field (name "MANUFACTURER") "Panasonic - ECG")
        (field (name "MANUFACTURER PART NUMBER") "ERJ-8ENF1800V")
      )
      (libsource (lib "eRCL") (part "ERJ-8ENF1800V"))
    )
    (comp (ref "R123")
      (value "5.1k")
      (footprint "R0805")
      (description "RES 5.10K OHM 1/8W 1% 0805 SMD")
      (fields
        (field (name "MANUFACTURER") "Panasonic - ECG")
        (field (name "MANUFACTURER PART NUMBER") "ERJ-6ENF5101V")
      )
      (libsource (lib "eRCL") (part "ERJ-6ENF5101V"))
    )
    (comp (ref "R124")
      (value "5.1k")
      (footprint "R0805")
      (description "RES 5.10K OHM 1/8W 1% 0805 SMD")
      (fields
        (field (name "MANUFACTURER") "Panasonic - ECG")
        (field (name "MANUFACTURER PART NUMBER") "ERJ-6ENF5101V")
      )
      (libsource (lib "eRCL") (part "ERJ-6ENF5101V"))
    )
    (comp (ref "R125")
      (value "5.1k")
      (footprint "R0805")
      (description "RES 5.10K OHM 1/8W 1% 0805 SMD")
      (fields
        (field (name "MANUFACTURER") "Panasonic - ECG")
        (field (name "MANUFACTURER PART NUMBER") "ERJ-6ENF5101V")
      )
      (libsource (lib "eRCL") (part "ERJ-6ENF5101V"))
    )
    (comp (ref "R129")
      (value "180")
      (footprint "R1206")
      (description "RES 180 OHM 1/4W 1% 1206 SMD")
      (fields
        (field (name "MANUFACTURER") "Panasonic - ECG")
        (field (name "MANUFACTURER PART NUMBER") "ERJ-8ENF1800V")
      )
      (libsource (lib "eRCL") (part "ERJ-8ENF1800V"))
    )
    (comp (ref "R130")
      (value "180")
      (footprint "R1206")
      (description "RES 180 OHM 1/4W 1% 1206 SMD")
      (fields
        (field (name "MANUFACTURER") "Panasonic - ECG")
        (field (name "MANUFACTURER PART NUMBER") "ERJ-8ENF1800V")
      )
      (libsource (lib "eRCL") (part "ERJ-8ENF1800V"))
    )
    (comp (ref "R131")
      (value "180")
      (footprint "R1206")
      (description "RES 180 OHM 1/4W 1% 1206 SMD")
      (fields
        (field (name "MANUFACTURER") "Panasonic - ECG")
        (field (name "MANUFACTURER PART NUMBER") "ERJ-8ENF1800V")
      )
      (libsource (lib "eRCL") (part "ERJ-8ENF1800V"))
    )
    (comp (ref "R135")
      (value "180")
      (footprint "R1206")
      (description "RES 180 OHM 1/4W 1% 1206 SMD")
      (fields
        (field (name "MANUFACTURER") "Panasonic - ECG")
        (field (name "MANUFACTURER PART NUMBER") "ERJ-8ENF1800V")
      )
      (libsource (lib "eRCL") (part "ERJ-8ENF1800V"))
    )
    (comp (ref "R136")
      (value "180")
      (footprint "R1206")
      (description "RES 180 OHM 1/4W 1% 1206 SMD")
      (fields
        (field (name "MANUFACTURER") "Panasonic - ECG")
        (field (name "MANUFACTURER PART NUMBER") "ERJ-8ENF1800V")
      )
      (libsource (lib "eRCL") (part "ERJ-8ENF1800V"))
    )
    (comp (ref "R137")
      (value "180")
      (footprint "R1206")
      (description "RES 180 OHM 1/4W 1% 1206 SMD")
      (fields
        (field (name "MANUFACTURER") "Panasonic - ECG")
        (field (name "MANUFACTURER PART NUMBER") "ERJ-8ENF1800V")
      )
      (libsource (lib "eRCL") (part "ERJ-8ENF1800V"))
    )
    (comp (ref "R141")
      (value "5.1k")
      (footprint "R0805")
      (description "RES 5.10K OHM 1/8W 1% 0805 SMD")
      (fields
        (field (name "MANUFACTURER") "Panasonic - ECG")
        (field (name "MANUFACTURER PART NUMBER") "ERJ-6ENF5101V")
      )
      (libsource (lib "eRCL") (part "ERJ-6ENF5101V"))
    )
    (comp (ref "R142")
      (value "5.1k")
      (footprint "R0805")
      (description "RES 5.10K OHM 1/8W 1% 0805 SMD")
      (fields
        (field (name "MANUFACTURER") "Panasonic - ECG")
        (field (name "MANUFACTURER PART NUMBER") "ERJ-6ENF5101V")
      )
      (libsource (lib "eRCL") (part "ERJ-6ENF5101V"))
    )
    (comp (ref "R143")
      (value "5.1k")
      (footprint "R0805")
      (description "RES 5.10K OHM 1/8W 1% 0805 SMD")
      (fields
        (field (name "MANUFACTURER") "Panasonic - ECG")
        (field (name "MANUFACTURER PART NUMBER") "ERJ-6ENF5101V")
      )
      (libsource (lib "eRCL") (part "ERJ-6ENF5101V"))
    )
    (comp (ref "R147")
      (value "180")
      (footprint "R1206")
      (description "RES 180 OHM 1/4W 1% 1206 SMD")
      (fields
        (field (name "MANUFACTURER") "Panasonic - ECG")
        (field (name "MANUFACTURER PART NUMBER") "ERJ-8ENF1800V")
      )
      (libsource (lib "eRCL") (part "ERJ-8ENF1800V"))
    )
    (comp (ref "R148")
      (value "180")
      (footprint "R1206")
      (description "RES 180 OHM 1/4W 1% 1206 SMD")
      (fields
        (field (name "MANUFACTURER") "Panasonic - ECG")
        (field (name "MANUFACTURER PART NUMBER") "ERJ-8ENF1800V")
      )
      (libsource (lib "eRCL") (part "ERJ-8ENF1800V"))
    )
    (comp (ref "R149")
      (value "180")
      (footprint "R1206")
      (description "RES 180 OHM 1/4W 1% 1206 SMD")
      (fields
        (field (name "MANUFACTURER") "Panasonic - ECG")
        (field (name "MANUFACTURER PART NUMBER") "ERJ-8ENF1800V")
      )
      (libsource (lib "eRCL") (part "ERJ-8ENF1800V"))
    )
    (comp (ref "R153")
      (value "180")
      (footprint "R1206")
      (description "RES 180 OHM 1/4W 1% 1206 SMD")
      (fields
        (field (name "MANUFACTURER") "Panasonic - ECG")
        (field (name "MANUFACTURER PART NUMBER") "ERJ-8ENF1800V")
      )
      (libsource (lib "eRCL") (part "ERJ-8ENF1800V"))
    )
    (comp (ref "R154")
      (value "180")
      (footprint "R1206")
      (description "RES 180 OHM 1/4W 1% 1206 SMD")
      (fields
        (field (name "MANUFACTURER") "Panasonic - ECG")
        (field (name "MANUFACTURER PART NUMBER") "ERJ-8ENF1800V")
      )
      (libsource (lib "eRCL") (part "ERJ-8ENF1800V"))
    )
    (comp (ref "R155")
      (value "180")
      (footprint "R1206")
      (description "RES 180 OHM 1/4W 1% 1206 SMD")
      (fields
        (field (name "MANUFACTURER") "Panasonic - ECG")
        (field (name "MANUFACTURER PART NUMBER") "ERJ-8ENF1800V")
      )
      (libsource (lib "eRCL") (part "ERJ-8ENF1800V"))
    )
    (comp (ref "R159")
      (value "5.1k")
      (footprint "R0805")
      (description "RES 5.10K OHM 1/8W 1% 0805 SMD")
      (fields
        (field (name "MANUFACTURER") "Panasonic - ECG")
        (field (name "MANUFACTURER PART NUMBER") "ERJ-6ENF5101V")
      )
      (libsource (lib "eRCL") (part "ERJ-6ENF5101V"))
    )
    (comp (ref "R160")
      (value "5.1k")
      (footprint "R0805")
      (description "RES 5.10K OHM 1/8W 1% 0805 SMD")
      (fields
        (field (name "MANUFACTURER") "Panasonic - ECG")
        (field (name "MANUFACTURER PART NUMBER") "ERJ-6ENF5101V")
      )
      (libsource (lib "eRCL") (part "ERJ-6ENF5101V"))
    )
    (comp (ref "R161")
      (value "5.1k")
      (footprint "R0805")
      (description "RES 5.10K OHM 1/8W 1% 0805 SMD")
      (fields
        (field (name "MANUFACTURER") "Panasonic - ECG")
        (field (name "MANUFACTURER PART NUMBER") "ERJ-6ENF5101V")
      )
      (libsource (lib "eRCL") (part "ERJ-6ENF5101V"))
    )
    (comp (ref "R165")
      (value "180")
      (footprint "R1206")
      (description "RES 180 OHM 1/4W 1% 1206 SMD")
      (fields
        (field (name "MANUFACTURER") "Panasonic - ECG")
        (field (name "MANUFACTURER PART NUMBER") "ERJ-8ENF1800V")
      )
      (libsource (lib "eRCL") (part "ERJ-8ENF1800V"))
    )
    (comp (ref "R166")
      (value "180")
      (footprint "R1206")
      (description "RES 180 OHM 1/4W 1% 1206 SMD")
      (fields
        (field (name "MANUFACTURER") "Panasonic - ECG")
        (field (name "MANUFACTURER PART NUMBER") "ERJ-8ENF1800V")
      )
      (libsource (lib "eRCL") (part "ERJ-8ENF1800V"))
    )
    (comp (ref "R167")
      (value "180")
      (footprint "R1206")
      (description "RES 180 OHM 1/4W 1% 1206 SMD")
      (fields
        (field (name "MANUFACTURER") "Panasonic - ECG")
        (field (name "MANUFACTURER PART NUMBER") "ERJ-8ENF1800V")
      )
      (libsource (lib "eRCL") (part "ERJ-8ENF1800V"))
    )
    (comp (ref "R171")
      (value "180")
      (footprint "R1206")
      (description "RES 180 OHM 1/4W 1% 1206 SMD")
      (fields
        (field (name "MANUFACTURER") "Panasonic - ECG")
        (field (name "MANUFACTURER PART NUMBER") "ERJ-8ENF1800V")
      )
      (libsource (lib "eRCL") (part "ERJ-8ENF1800V"))
    )
    (comp (ref "R172")
      (value "180")
      (footprint "R1206")
      (description "RES 180 OHM 1/4W 1% 1206 SMD")
      (fields
        (field (name "MANUFACTURER") "Panasonic - ECG")
        (field (name "MANUFACTURER PART NUMBER") "ERJ-8ENF1800V")
      )
      (libsource (lib "eRCL") (part "ERJ-8ENF1800V"))
    )
    (comp (ref "R173")
      (value "180")
      (footprint "R1206")
      (description "RES 180 OHM 1/4W 1% 1206 SMD")
      (fields
        (field (name "MANUFACTURER") "Panasonic - ECG")
        (field (name "MANUFACTURER PART NUMBER") "ERJ-8ENF1800V")
      )
      (libsource (lib "eRCL") (part "ERJ-8ENF1800V"))
    )
    (comp (ref "R177")
      (value "5.1k")
      (footprint "R0805")
      (description "RES 5.10K OHM 1/8W 1% 0805 SMD")
      (fields
        (field (name "MANUFACTURER") "Panasonic - ECG")
        (field (name "MANUFACTURER PART NUMBER") "ERJ-6ENF5101V")
      )
      (libsource (lib "eRCL") (part "ERJ-6ENF5101V"))
    )
    (comp (ref "R178")
      (value "5.1k")
      (footprint "R0805")
      (description "RES 5.10K OHM 1/8W 1% 0805 SMD")
      (fields
        (field (name "MANUFACTURER") "Panasonic - ECG")
        (field (name "MANUFACTURER PART NUMBER") "ERJ-6ENF5101V")
      )
      (libsource (lib "eRCL") (part "ERJ-6ENF5101V"))
    )
    (comp (ref "R179")
      (value "5.1k")
      (footprint "R0805")
      (description "RES 5.10K OHM 1/8W 1% 0805 SMD")
      (fields
        (field (name "MANUFACTURER") "Panasonic - ECG")
        (field (name "MANUFACTURER PART NUMBER") "ERJ-6ENF5101V")
      )
      (libsource (lib "eRCL") (part "ERJ-6ENF5101V"))
    )
    (comp (ref "R183")
      (value "180")
      (footprint "R1206")
      (description "RES 180 OHM 1/4W 1% 1206 SMD")
      (fields
        (field (name "MANUFACTURER") "Panasonic - ECG")
        (field (name "MANUFACTURER PART NUMBER") "ERJ-8ENF1800V")
      )
      (libsource (lib "eRCL") (part "ERJ-8ENF1800V"))
    )
    (comp (ref "R184")
      (value "180")
      (footprint "R1206")
      (description "RES 180 OHM 1/4W 1% 1206 SMD")
      (fields
        (field (name "MANUFACTURER") "Panasonic - ECG")
        (field (name "MANUFACTURER PART NUMBER") "ERJ-8ENF1800V")
      )
      (libsource (lib "eRCL") (part "ERJ-8ENF1800V"))
    )
    (comp (ref "R185")
      (value "180")
      (footprint "R1206")
      (description "RES 180 OHM 1/4W 1% 1206 SMD")
      (fields
        (field (name "MANUFACTURER") "Panasonic - ECG")
        (field (name "MANUFACTURER PART NUMBER") "ERJ-8ENF1800V")
      )
      (libsource (lib "eRCL") (part "ERJ-8ENF1800V"))
    )
    (comp (ref "R189")
      (value "180")
      (footprint "R1206")
      (description "RES 180 OHM 1/4W 1% 1206 SMD")
      (fields
        (field (name "MANUFACTURER") "Panasonic - ECG")
        (field (name "MANUFACTURER PART NUMBER") "ERJ-8ENF1800V")
      )
      (libsource (lib "eRCL") (part "ERJ-8ENF1800V"))
    )
    (comp (ref "R190")
      (value "180")
      (footprint "R1206")
      (description "RES 180 OHM 1/4W 1% 1206 SMD")
      (fields
        (field (name "MANUFACTURER") "Panasonic - ECG")
        (field (name "MANUFACTURER PART NUMBER") "ERJ-8ENF1800V")
      )
      (libsource (lib "eRCL") (part "ERJ-8ENF1800V"))
    )
    (comp (ref "R191")
      (value "180")
      (footprint "R1206")
      (description "RES 180 OHM 1/4W 1% 1206 SMD")
      (fields
        (field (name "MANUFACTURER") "Panasonic - ECG")
        (field (name "MANUFACTURER PART NUMBER") "ERJ-8ENF1800V")
      )
      (libsource (lib "eRCL") (part "ERJ-8ENF1800V"))
    )
    (comp (ref "R195")
      (value "5.1k")
      (footprint "R0805")
      (description "RES 5.10K OHM 1/8W 1% 0805 SMD")
      (fields
        (field (name "MANUFACTURER") "Panasonic - ECG")
        (field (name "MANUFACTURER PART NUMBER") "ERJ-6ENF5101V")
      )
      (libsource (lib "eRCL") (part "ERJ-6ENF5101V"))
    )
    (comp (ref "R196")
      (value "5.1k")
      (footprint "R0805")
      (description "RES 5.10K OHM 1/8W 1% 0805 SMD")
      (fields
        (field (name "MANUFACTURER") "Panasonic - ECG")
        (field (name "MANUFACTURER PART NUMBER") "ERJ-6ENF5101V")
      )
      (libsource (lib "eRCL") (part "ERJ-6ENF5101V"))
    )
    (comp (ref "R197")
      (value "5.1k")
      (footprint "R0805")
      (description "RES 5.10K OHM 1/8W 1% 0805 SMD")
      (fields
        (field (name "MANUFACTURER") "Panasonic - ECG")
        (field (name "MANUFACTURER PART NUMBER") "ERJ-6ENF5101V")
      )
      (libsource (lib "eRCL") (part "ERJ-6ENF5101V"))
    )
    (comp (ref "R201")
      (value "180")
      (footprint "R1206")
      (description "RES 180 OHM 1/4W 1% 1206 SMD")
      (fields
        (field (name "MANUFACTURER") "Panasonic - ECG")
        (field (name "MANUFACTURER PART NUMBER") "ERJ-8ENF1800V")
      )
      (libsource (lib "eRCL") (part "ERJ-8ENF1800V"))
    )
    (comp (ref "R202")
      (value "180")
      (footprint "R1206")
      (description "RES 180 OHM 1/4W 1% 1206 SMD")
      (fields
        (field (name "MANUFACTURER") "Panasonic - ECG")
        (field (name "MANUFACTURER PART NUMBER") "ERJ-8ENF1800V")
      )
      (libsource (lib "eRCL") (part "ERJ-8ENF1800V"))
    )
    (comp (ref "R203")
      (value "180")
      (footprint "R1206")
      (description "RES 180 OHM 1/4W 1% 1206 SMD")
      (fields
        (field (name "MANUFACTURER") "Panasonic - ECG")
        (field (name "MANUFACTURER PART NUMBER") "ERJ-8ENF1800V")
      )
      (libsource (lib "eRCL") (part "ERJ-8ENF1800V"))
    )
    (comp (ref "R207")
      (value "180")
      (footprint "R1206")
      (description "RES 180 OHM 1/4W 1% 1206 SMD")
      (fields
        (field (name "MANUFACTURER") "Panasonic - ECG")
        (field (name "MANUFACTURER PART NUMBER") "ERJ-8ENF1800V")
      )
      (libsource (lib "eRCL") (part "ERJ-8ENF1800V"))
    )
    (comp (ref "R208")
      (value "180")
      (footprint "R1206")
      (description "RES 180 OHM 1/4W 1% 1206 SMD")
      (fields
        (field (name "MANUFACTURER") "Panasonic - ECG")
        (field (name "MANUFACTURER PART NUMBER") "ERJ-8ENF1800V")
      )
      (libsource (lib "eRCL") (part "ERJ-8ENF1800V"))
    )
    (comp (ref "R209")
      (value "180")
      (footprint "R1206")
      (description "RES 180 OHM 1/4W 1% 1206 SMD")
      (fields
        (field (name "MANUFACTURER") "Panasonic - ECG")
        (field (name "MANUFACTURER PART NUMBER") "ERJ-8ENF1800V")
      )
      (libsource (lib "eRCL") (part "ERJ-8ENF1800V"))
    )
    (comp (ref "R213")
      (value "5.1k")
      (footprint "R0805")
      (description "RES 5.10K OHM 1/8W 1% 0805 SMD")
      (fields
        (field (name "MANUFACTURER") "Panasonic - ECG")
        (field (name "MANUFACTURER PART NUMBER") "ERJ-6ENF5101V")
      )
      (libsource (lib "eRCL") (part "ERJ-6ENF5101V"))
    )
    (comp (ref "R214")
      (value "5.1k")
      (footprint "R0805")
      (description "RES 5.10K OHM 1/8W 1% 0805 SMD")
      (fields
        (field (name "MANUFACTURER") "Panasonic - ECG")
        (field (name "MANUFACTURER PART NUMBER") "ERJ-6ENF5101V")
      )
      (libsource (lib "eRCL") (part "ERJ-6ENF5101V"))
    )
    (comp (ref "R215")
      (value "5.1k")
      (footprint "R0805")
      (description "RES 5.10K OHM 1/8W 1% 0805 SMD")
      (fields
        (field (name "MANUFACTURER") "Panasonic - ECG")
        (field (name "MANUFACTURER PART NUMBER") "ERJ-6ENF5101V")
      )
      (libsource (lib "eRCL") (part "ERJ-6ENF5101V"))
    )
    (comp (ref "R219")
      (value "180")
      (footprint "R1206")
      (description "RES 180 OHM 1/4W 1% 1206 SMD")
      (fields
        (field (name "MANUFACTURER") "Panasonic - ECG")
        (field (name "MANUFACTURER PART NUMBER") "ERJ-8ENF1800V")
      )
      (libsource (lib "eRCL") (part "ERJ-8ENF1800V"))
    )
    (comp (ref "R220")
      (value "180")
      (footprint "R1206")
      (description "RES 180 OHM 1/4W 1% 1206 SMD")
      (fields
        (field (name "MANUFACTURER") "Panasonic - ECG")
        (field (name "MANUFACTURER PART NUMBER") "ERJ-8ENF1800V")
      )
      (libsource (lib "eRCL") (part "ERJ-8ENF1800V"))
    )
    (comp (ref "R221")
      (value "180")
      (footprint "R1206")
      (description "RES 180 OHM 1/4W 1% 1206 SMD")
      (fields
        (field (name "MANUFACTURER") "Panasonic - ECG")
        (field (name "MANUFACTURER PART NUMBER") "ERJ-8ENF1800V")
      )
      (libsource (lib "eRCL") (part "ERJ-8ENF1800V"))
    )
    (comp (ref "R225")
      (value "180")
      (footprint "R1206")
      (description "RES 180 OHM 1/4W 1% 1206 SMD")
      (fields
        (field (name "MANUFACTURER") "Panasonic - ECG")
        (field (name "MANUFACTURER PART NUMBER") "ERJ-8ENF1800V")
      )
      (libsource (lib "eRCL") (part "ERJ-8ENF1800V"))
    )
    (comp (ref "R226")
      (value "180")
      (footprint "R1206")
      (description "RES 180 OHM 1/4W 1% 1206 SMD")
      (fields
        (field (name "MANUFACTURER") "Panasonic - ECG")
        (field (name "MANUFACTURER PART NUMBER") "ERJ-8ENF1800V")
      )
      (libsource (lib "eRCL") (part "ERJ-8ENF1800V"))
    )
    (comp (ref "R227")
      (value "180")
      (footprint "R1206")
      (description "RES 180 OHM 1/4W 1% 1206 SMD")
      (fields
        (field (name "MANUFACTURER") "Panasonic - ECG")
        (field (name "MANUFACTURER PART NUMBER") "ERJ-8ENF1800V")
      )
      (libsource (lib "eRCL") (part "ERJ-8ENF1800V"))
    )
    (comp (ref "U19")
      (value "IS/SN74HC573DWZ")
      (footprint "SOIC300-20")
      (description "Octal D-Type Transparent Latch with 3-State Outputs")
      (fields
        (field (name "MANUFACTURER") "NXP Semiconductors")
        (field (name "MANUFACTURER PART NUMBER") "74HC573D-T")
        (field (name "SOURCE") "Digikey")
      )
      (libsource (lib "ScoreBoard") (part "IS/SN74HC573DWZ"))
    )
    (comp (ref "U20")
      (value "IS/SN74HC573DWZ")
      (footprint "SOIC300-20")
      (description "Octal D-Type Transparent Latch with 3-State Outputs")
      (fields
        (field (name "MANUFACTURER") "NXP Semiconductors")
        (field (name "MANUFACTURER PART NUMBER") "74HC573D-T")
        (field (name "SOURCE") "Digikey")
      )
      (libsource (lib "ScoreBoard") (part "IS/SN74HC573DWZ"))
    )
    (comp (ref "U21")
      (value "IS/SN74HC573DWZ")
      (footprint "SOIC300-20")
      (description "Octal D-Type Transparent Latch with 3-State Outputs")
      (fields
        (field (name "MANUFACTURER") "NXP Semiconductors")
        (field (name "MANUFACTURER PART NUMBER") "74HC573D-T")
        (field (name "SOURCE") "Digikey")
      )
      (libsource (lib "ScoreBoard") (part "IS/SN74HC573DWZ"))
    )
  )
  (nets
    (net (code "1") (name "/8V") (class "Default")
      (node (ref "DS1") (pin "1") (pinfunction "A_1") (pintype "passive"))
      (node (ref "DS101") (pin "1") (pinfunction "A_1") (pintype "passive"))
      (node (ref "DS109") (pin "1") (pinfunction "A_1") (pintype "passive"))
      (node (ref "DS111") (pin "1") (pinfunction "A_1") (pintype "passive"))
      (node (ref "DS113") (pin "1") (pinfunction "A_1") (pintype "passive"))
      (node (ref "DS121") (pin "1") (pinfunction "A_1") (pintype "passive"))
      (node (ref "DS123") (pin "1") (pinfunction "A_1") (pintype "passive"))
      (node (ref "DS125") (pin "1") (pinfunction "A_1") (pintype "passive"))
      (node (ref "DS13") (pin "1") (pinfunction "A_1") (pintype "passive"))
      (node (ref "DS133") (pin "1") (pinfunction "A_1") (pintype "passive"))
      (node (ref "DS135") (pin "1") (pinfunction "A_1") (pintype "passive"))
      (node (ref "DS137") (pin "1") (pinfunction "A_1") (pintype "passive"))
      (node (ref "DS145") (pin "1") (pinfunction "A_1") (pintype "passive"))
      (node (ref "DS147") (pin "1") (pinfunction "A_1") (pintype "passive"))
      (node (ref "DS149") (pin "1") (pinfunction "A_1") (pintype "passive"))
      (node (ref "DS15") (pin "1") (pinfunction "A_1") (pintype "passive"))
      (node (ref "DS157") (pin "1") (pinfunction "A_1") (pintype "passive"))
      (node (ref "DS159") (pin "1") (pinfunction "A_1") (pintype "passive"))
      (node (ref "DS161") (pin "1") (pinfunction "A_1") (pintype "passive"))
      (node (ref "DS17") (pin "1") (pinfunction "A_1") (pintype "passive"))
      (node (ref "DS25") (pin "1") (pinfunction "A_1") (pintype "passive"))
      (node (ref "DS27") (pin "1") (pinfunction "A_1") (pintype "passive"))
      (node (ref "DS29") (pin "1") (pinfunction "A_1") (pintype "passive"))
      (node (ref "DS3") (pin "1") (pinfunction "A_1") (pintype "passive"))
      (node (ref "DS37") (pin "1") (pinfunction "A_1") (pintype "passive"))
      (node (ref "DS39") (pin "1") (pinfunction "A_1") (pintype "passive"))
      (node (ref "DS41") (pin "1") (pinfunction "A_1") (pintype "passive"))
      (node (ref "DS49") (pin "1") (pinfunction "A_1") (pintype "passive"))
      (node (ref "DS5") (pin "1") (pinfunction "A_1") (pintype "passive"))
      (node (ref "DS51") (pin "1") (pinfunction "A_1") (pintype "passive"))
      (node (ref "DS53") (pin "1") (pinfunction "A_1") (pintype "passive"))
      (node (ref "DS61") (pin "1") (pinfunction "A_1") (pintype "passive"))
      (node (ref "DS63") (pin "1") (pinfunction "A_1") (pintype "passive"))
      (node (ref "DS65") (pin "1") (pinfunction "A_1") (pintype "passive"))
      (node (ref "DS73") (pin "1") (pinfunction "A_1") (pintype "passive"))
      (node (ref "DS75") (pin "1") (pinfunction "A_1") (pintype "passive"))
      (node (ref "DS77") (pin "1") (pinfunction "A_1") (pintype "passive"))
      (node (ref "DS85") (pin "1") (pinfunction "A_1") (pintype "passive"))
      (node (ref "DS87") (pin "1") (pinfunction "A_1") (pintype "passive"))
      (node (ref "DS89") (pin "1") (pinfunction "A_1") (pintype "passive"))
      (node (ref "DS97") (pin "1") (pinfunction "A_1") (pintype "passive"))
      (node (ref "DS99") (pin "1") (pinfunction "A_1") (pintype "passive"))
    )
    (net (code "2") (name "/CLK0") (class "Default")
      (node (ref "U19") (pin "11") (pinfunction "LE_11") (pintype "input"))
    )
    (net (code "3") (name "/CLK1") (class "Default")
      (node (ref "U20") (pin "11") (pinfunction "LE_11") (pintype "input"))
    )
    (net (code "4") (name "/CLK2") (class "Default")
      (node (ref "U21") (pin "11") (pinfunction "LE_11") (pintype "input"))
    )
    (net (code "5") (name "/D0") (class "Default")
      (node (ref "U19") (pin "2") (pinfunction "D1_2") (pintype "input"))
      (node (ref "U20") (pin "2") (pinfunction "D1_2") (pintype "input"))
      (node (ref "U21") (pin "2") (pinfunction "D1_2") (pintype "input"))
    )
    (net (code "6") (name "/D1") (class "Default")
      (node (ref "U19") (pin "3") (pinfunction "D2_3") (pintype "input"))
      (node (ref "U20") (pin "3") (pinfunction "D2_3") (pintype "input"))
      (node (ref "U21") (pin "3") (pinfunction "D2_3") (pintype "input"))
    )
    (net (code "7") (name "/D2") (class "Default")
      (node (ref "U19") (pin "4") (pinfunction "D3_4") (pintype "input"))
      (node (ref "U20") (pin "4") (pinfunction "D3_4") (pintype "input"))
      (node (ref "U21") (pin "4") (pinfunction "D3_4") (pintype "input"))
    )
    (net (code "8") (name "/D3") (class "Default")
      (node (ref "U19") (pin "5") (pinfunction "D4_5") (pintype "input"))
      (node (ref "U20") (pin "5") (pinfunction "D4_5") (pintype "input"))
      (node (ref "U21") (pin "5") (pinfunction "D4_5") (pintype "input"))
    )
    (net (code "9") (name "/D4") (class "Default")
      (node (ref "U19") (pin "6") (pinfunction "D5_6") (pintype "input"))
      (node (ref "U20") (pin "6") (pinfunction "D5_6") (pintype "input"))
      (node (ref "U21") (pin "6") (pinfunction "D5_6") (pintype "input"))
    )
    (net (code "10") (name "/D5") (class "Default")
      (node (ref "U19") (pin "7") (pinfunction "D6_7") (pintype "input"))
      (node (ref "U20") (pin "7") (pinfunction "D6_7") (pintype "input"))
      (node (ref "U21") (pin "7") (pinfunction "D6_7") (pintype "input"))
    )
    (net (code "11") (name "/D6") (class "Default")
      (node (ref "U19") (pin "8") (pinfunction "D7_8") (pintype "input"))
      (node (ref "U20") (pin "8") (pinfunction "D7_8") (pintype "input"))
      (node (ref "U21") (pin "8") (pinfunction "D7_8") (pintype "input"))
    )
    (net (code "12") (name "/D7") (class "Default")
      (node (ref "U19") (pin "9") (pinfunction "D8_9") (pintype "input"))
      (node (ref "U20") (pin "9") (pinfunction "D8_9") (pintype "input"))
      (node (ref "U21") (pin "9") (pinfunction "D8_9") (pintype "input"))
    )
    (net (code "13") (name "/LAMP0") (class "Default")
      (node (ref "U19") (pin "12") (pinfunction "Q8_12") (pintype "tri_state"))
    )
    (net (code "14") (name "/LAMP1") (class "Default")
      (node (ref "U20") (pin "12") (pinfunction "Q8_12") (pintype "tri_state"))
    )
    (net (code "15") (name "/LAMP2") (class "Default")
      (node (ref "U21") (pin "12") (pinfunction "Q8_12") (pintype "tri_state"))
    )
    (net (code "16") (name "/LED_OE") (class "Default")
      (node (ref "U19") (pin "1") (pinfunction "~{OE}_1") (pintype "input"))
      (node (ref "U20") (pin "1") (pinfunction "~{OE}_1") (pintype "input"))
      (node (ref "U21") (pin "1") (pinfunction "~{OE}_1") (pintype "input"))
    )
    (net (code "17") (name "GND") (class "Default")
      (node (ref "C47") (pin "2") (pinfunction "2_2") (pintype "passive"))
      (node (ref "C48") (pin "2") (pinfunction "2_2") (pintype "passive"))
      (node (ref "C49") (pin "2") (pinfunction "2_2") (pintype "passive"))
      (node (ref "Q22") (pin "2") (pinfunction "E_2") (pintype "passive"))
      (node (ref "Q23") (pin "2") (pinfunction "E_2") (pintype "passive"))
      (node (ref "Q24") (pin "2") (pinfunction "E_2") (pintype "passive"))
      (node (ref "Q28") (pin "2") (pinfunction "E_2") (pintype "passive"))
      (node (ref "Q29") (pin "2") (pinfunction "E_2") (pintype "passive"))
      (node (ref "Q30") (pin "2") (pinfunction "E_2") (pintype "passive"))
      (node (ref "Q34") (pin "2") (pinfunction "E_2") (pintype "passive"))
      (node (ref "Q35") (pin "2") (pinfunction "E_2") (pintype "passive"))
      (node (ref "Q36") (pin "2") (pinfunction "E_2") (pintype "passive"))
      (node (ref "Q40") (pin "2") (pinfunction "E_2") (pintype "passive"))
      (node (ref "Q41") (pin "2") (pinfunction "E_2") (pintype "passive"))
      (node (ref "Q42") (pin "2") (pinfunction "E_2") (pintype "passive"))
      (node (ref "Q46") (pin "2") (pinfunction "E_2") (pintype "passive"))
      (node (ref "Q47") (pin "2") (pinfunction "E_2") (pintype "passive"))
      (node (ref "Q48") (pin "2") (pinfunction "E_2") (pintype "passive"))
      (node (ref "Q52") (pin "2") (pinfunction "E_2") (pintype "passive"))
      (node (ref "Q53") (pin "2") (pinfunction "E_2") (pintype "passive"))
      (node (ref "Q54") (pin "2") (pinfunction "E_2") (pintype "passive"))
      (node (ref "Q58") (pin "2") (pinfunction "E_2") (pintype "passive"))
      (node (ref "Q59") (pin "2") (pinfunction "E_2") (pintype "passive"))
      (node (ref "Q60") (pin "2") (pinfunction "E_2") (pintype "passive"))
      (node (ref "U19") (pin "10") (pinfunction "GND_10") (pintype "power_in"))
      (node (ref "U20") (pin "10") (pinfunction "GND_10") (pintype "power_in"))
      (node (ref "U21") (pin "10") (pinfunction "GND_10") (pintype "power_in"))
    )
    (net (code "18") (name "Net-(DS1-K)") (class "Default")
      (node (ref "DS1") (pin "2") (pinfunction "K_2") (pintype "passive"))
      (node (ref "DS2") (pin "1") (pinfunction "A_1") (pintype "passive"))
    )
    (net (code "19") (name "Net-(DS2-K)") (class "Default")
      (node (ref "DS2") (pin "2") (pinfunction "K_2") (pintype "passive"))
      (node (ref "R111") (pin "2") (pinfunction "2_2") (pintype "passive"))
    )
    (net (code "20") (name "Net-(DS3-K)") (class "Default")
      (node (ref "DS3") (pin "2") (pinfunction "K_2") (pintype "passive"))
      (node (ref "DS4") (pin "1") (pinfunction "A_1") (pintype "passive"))
    )
    (net (code "21") (name "Net-(DS4-K)") (class "Default")
      (node (ref "DS4") (pin "2") (pinfunction "K_2") (pintype "passive"))
      (node (ref "R112") (pin "2") (pinfunction "2_2") (pintype "passive"))
    )
    (net (code "22") (name "Net-(DS5-K)") (class "Default")
      (node (ref "DS5") (pin "2") (pinfunction "K_2") (pintype "passive"))
      (node (ref "DS6") (pin "1") (pinfunction "A_1") (pintype "passive"))
    )
    (net (code "23") (name "Net-(DS6-K)") (class "Default")
      (node (ref "DS6") (pin "2") (pinfunction "K_2") (pintype "passive"))
      (node (ref "R113") (pin "2") (pinfunction "2_2") (pintype "passive"))
    )
    (net (code "24") (name "Net-(DS13-K)") (class "Default")
      (node (ref "DS13") (pin "2") (pinfunction "K_2") (pintype "passive"))
      (node (ref "DS14") (pin "1") (pinfunction "A_1") (pintype "passive"))
    )
    (net (code "25") (name "Net-(DS14-K)") (class "Default")
      (node (ref "DS14") (pin "2") (pinfunction "K_2") (pintype "passive"))
      (node (ref "R117") (pin "2") (pinfunction "2_2") (pintype "passive"))
    )
    (net (code "26") (name "Net-(DS15-K)") (class "Default")
      (node (ref "DS15") (pin "2") (pinfunction "K_2") (pintype "passive"))
      (node (ref "DS16") (pin "1") (pinfunction "A_1") (pintype "passive"))
    )
    (net (code "27") (name "Net-(DS16-K)") (class "Default")
      (node (ref "DS16") (pin "2") (pinfunction "K_2") (pintype "passive"))
      (node (ref "R118") (pin "2") (pinfunction "2_2") (pintype "passive"))
    )
    (net (code "28") (name "Net-(DS17-K)") (class "Default")
      (node (ref "DS17") (pin "2") (pinfunction "K_2") (pintype "passive"))
      (node (ref "DS18") (pin "1") (pinfunction "A_1") (pintype "passive"))
    )
    (net (code "29") (name "Net-(DS18-K)") (class "Default")
      (node (ref "DS18") (pin "2") (pinfunction "K_2") (pintype "passive"))
      (node (ref "R119") (pin "2") (pinfunction "2_2") (pintype "passive"))
    )
    (net (code "30") (name "Net-(DS25-K)") (class "Default")
      (node (ref "DS25") (pin "2") (pinfunction "K_2") (pintype "passive"))
      (node (ref "DS26") (pin "1") (pinfunction "A_1") (pintype "passive"))
    )
    (net (code "31") (name "Net-(DS26-K)") (class "Default")
      (node (ref "DS26") (pin "2") (pinfunction "K_2") (pintype "passive"))
      (node (ref "R129") (pin "2") (pinfunction "2_2") (pintype "passive"))
    )
    (net (code "32") (name "Net-(DS27-K)") (class "Default")
      (node (ref "DS27") (pin "2") (pinfunction "K_2") (pintype "passive"))
      (node (ref "DS28") (pin "1") (pinfunction "A_1") (pintype "passive"))
    )
    (net (code "33") (name "Net-(DS28-K)") (class "Default")
      (node (ref "DS28") (pin "2") (pinfunction "K_2") (pintype "passive"))
      (node (ref "R130") (pin "2") (pinfunction "2_2") (pintype "passive"))
    )
    (net (code "34") (name "Net-(DS29-K)") (class "Default")
      (node (ref "DS29") (pin "2") (pinfunction "K_2") (pintype "passive"))
      (node (ref "DS30") (pin "1") (pinfunction "A_1") (pintype "passive"))
    )
    (net (code "35") (name "Net-(DS30-K)") (class "Default")
      (node (ref "DS30") (pin "2") (pinfunction "K_2") (pintype "passive"))
      (node (ref "R131") (pin "2") (pinfunction "2_2") (pintype "passive"))
    )
    (net (code "36") (name "Net-(DS37-K)") (class "Default")
      (node (ref "DS37") (pin "2") (pinfunction "K_2") (pintype "passive"))
      (node (ref "DS38") (pin "1") (pinfunction "A_1") (pintype "passive"))
    )
    (net (code "37") (name "Net-(DS38-K)") (class "Default")
      (node (ref "DS38") (pin "2") (pinfunction "K_2") (pintype "passive"))
      (node (ref "R135") (pin "2") (pinfunction "2_2") (pintype "passive"))
    )
    (net (code "38") (name "Net-(DS39-K)") (class "Default")
      (node (ref "DS39") (pin "2") (pinfunction "K_2") (pintype "passive"))
      (node (ref "DS40") (pin "1") (pinfunction "A_1") (pintype "passive"))
    )
    (net (code "39") (name "Net-(DS40-K)") (class "Default")
      (node (ref "DS40") (pin "2") (pinfunction "K_2") (pintype "passive"))
      (node (ref "R136") (pin "2") (pinfunction "2_2") (pintype "passive"))
    )
    (net (code "40") (name "Net-(DS41-K)") (class "Default")
      (node (ref "DS41") (pin "2") (pinfunction "K_2") (pintype "passive"))
      (node (ref "DS42") (pin "1") (pinfunction "A_1") (pintype "passive"))
    )
    (net (code "41") (name "Net-(DS42-K)") (class "Default")
      (node (ref "DS42") (pin "2") (pinfunction "K_2") (pintype "passive"))
      (node (ref "R137") (pin "2") (pinfunction "2_2") (pintype "passive"))
    )
    (net (code "42") (name "Net-(DS49-K)") (class "Default")
      (node (ref "DS49") (pin "2") (pinfunction "K_2") (pintype "passive"))
      (node (ref "DS50") (pin "1") (pinfunction "A_1") (pintype "passive"))
    )
    (net (code "43") (name "Net-(DS50-K)") (class "Default")
      (node (ref "DS50") (pin "2") (pinfunction "K_2") (pintype "passive"))
      (node (ref "R147") (pin "2") (pinfunction "2_2") (pintype "passive"))
    )
    (net (code "44") (name "Net-(DS51-K)") (class "Default")
      (node (ref "DS51") (pin "2") (pinfunction "K_2") (pintype "passive"))
      (node (ref "DS52") (pin "1") (pinfunction "A_1") (pintype "passive"))
    )
    (net (code "45") (name "Net-(DS52-K)") (class "Default")
      (node (ref "DS52") (pin "2") (pinfunction "K_2") (pintype "passive"))
      (node (ref "R148") (pin "2") (pinfunction "2_2") (pintype "passive"))
    )
    (net (code "46") (name "Net-(DS53-K)") (class "Default")
      (node (ref "DS53") (pin "2") (pinfunction "K_2") (pintype "passive"))
      (node (ref "DS54") (pin "1") (pinfunction "A_1") (pintype "passive"))
    )
    (net (code "47") (name "Net-(DS54-K)") (class "Default")
      (node (ref "DS54") (pin "2") (pinfunction "K_2") (pintype "passive"))
      (node (ref "R149") (pin "2") (pinfunction "2_2") (pintype "passive"))
    )
    (net (code "48") (name "Net-(DS61-K)") (class "Default")
      (node (ref "DS61") (pin "2") (pinfunction "K_2") (pintype "passive"))
      (node (ref "DS62") (pin "1") (pinfunction "A_1") (pintype "passive"))
    )
    (net (code "49") (name "Net-(DS62-K)") (class "Default")
      (node (ref "DS62") (pin "2") (pinfunction "K_2") (pintype "passive"))
      (node (ref "R153") (pin "2") (pinfunction "2_2") (pintype "passive"))
    )
    (net (code "50") (name "Net-(DS63-K)") (class "Default")
      (node (ref "DS63") (pin "2") (pinfunction "K_2") (pintype "passive"))
      (node (ref "DS64") (pin "1") (pinfunction "A_1") (pintype "passive"))
    )
    (net (code "51") (name "Net-(DS64-K)") (class "Default")
      (node (ref "DS64") (pin "2") (pinfunction "K_2") (pintype "passive"))
      (node (ref "R154") (pin "2") (pinfunction "2_2") (pintype "passive"))
    )
    (net (code "52") (name "Net-(DS65-K)") (class "Default")
      (node (ref "DS65") (pin "2") (pinfunction "K_2") (pintype "passive"))
      (node (ref "DS66") (pin "1") (pinfunction "A_1") (pintype "passive"))
    )
    (net (code "53") (name "Net-(DS66-K)") (class "Default")
      (node (ref "DS66") (pin "2") (pinfunction "K_2") (pintype "passive"))
      (node (ref "R155") (pin "2") (pinfunction "2_2") (pintype "passive"))
    )
    (net (code "54") (name "Net-(DS73-K)") (class "Default")
      (node (ref "DS73") (pin "2") (pinfunction "K_2") (pintype "passive"))
      (node (ref "DS74") (pin "1") (pinfunction "A_1") (pintype "passive"))
    )
    (net (code "55") (name "Net-(DS74-K)") (class "Default")
      (node (ref "DS74") (pin "2") (pinfunction "K_2") (pintype "passive"))
      (node (ref "R165") (pin "2") (pinfunction "2_2") (pintype "passive"))
    )
    (net (code "56") (name "Net-(DS75-K)") (class "Default")
      (node (ref "DS75") (pin "2") (pinfunction "K_2") (pintype "passive"))
      (node (ref "DS76") (pin "1") (pinfunction "A_1") (pintype "passive"))
    )
    (net (code "57") (name "Net-(DS76-K)") (class "Default")
      (node (ref "DS76") (pin "2") (pinfunction "K_2") (pintype "passive"))
      (node (ref "R166") (pin "2") (pinfunction "2_2") (pintype "passive"))
    )
    (net (code "58") (name "Net-(DS77-K)") (class "Default")
      (node (ref "DS77") (pin "2") (pinfunction "K_2") (pintype "passive"))
      (node (ref "DS78") (pin "1") (pinfunction "A_1") (pintype "passive"))
    )
    (net (code "59") (name "Net-(DS78-K)") (class "Default")
      (node (ref "DS78") (pin "2") (pinfunction "K_2") (pintype "passive"))
      (node (ref "R167") (pin "2") (pinfunction "2_2") (pintype "passive"))
    )
    (net (code "60") (name "Net-(DS85-K)") (class "Default")
      (node (ref "DS85") (pin "2") (pinfunction "K_2") (pintype "passive"))
      (node (ref "DS86") (pin "1") (pinfunction "A_1") (pintype "passive"))
    )
    (net (code "61") (name "Net-(DS86-K)") (class "Default")
      (node (ref "DS86") (pin "2") (pinfunction "K_2") (pintype "passive"))
      (node (ref "R171") (pin "2") (pinfunction "2_2") (pintype "passive"))
    )
    (net (code "62") (name "Net-(DS87-K)") (class "Default")
      (node (ref "DS87") (pin "2") (pinfunction "K_2") (pintype "passive"))
      (node (ref "DS88") (pin "1") (pinfunction "A_1") (pintype "passive"))
    )
    (net (code "63") (name "Net-(DS88-K)") (class "Default")
      (node (ref "DS88") (pin "2") (pinfunction "K_2") (pintype "passive"))
      (node (ref "R172") (pin "2") (pinfunction "2_2") (pintype "passive"))
    )
    (net (code "64") (name "Net-(DS89-K)") (class "Default")
      (node (ref "DS89") (pin "2") (pinfunction "K_2") (pintype "passive"))
      (node (ref "DS90") (pin "1") (pinfunction "A_1") (pintype "passive"))
    )
    (net (code "65") (name "Net-(DS90-K)") (class "Default")
      (node (ref "DS90") (pin "2") (pinfunction "K_2") (pintype "passive"))
      (node (ref "R173") (pin "2") (pinfunction "2_2") (pintype "passive"))
    )
    (net (code "66") (name "Net-(DS97-K)") (class "Default")
      (node (ref "DS97") (pin "2") (pinfunction "K_2") (pintype "passive"))
      (node (ref "DS98") (pin "1") (pinfunction "A_1") (pintype "passive"))
    )
    (net (code "67") (name "Net-(DS98-K)") (class "Default")
      (node (ref "DS98") (pin "2") (pinfunction "K_2") (pintype "passive"))
      (node (ref "R183") (pin "2") (pinfunction "2_2") (pintype "passive"))
    )
    (net (code "68") (name "Net-(DS100-A)") (class "Default")
      (node (ref "DS100") (pin "1") (pinfunction "A_1") (pintype "passive"))
      (node (ref "DS99") (pin "2") (pinfunction "K_2") (pintype "passive"))
    )
    (net (code "69") (name "Net-(DS100-K)") (class "Default")
      (node (ref "DS100") (pin "2") (pinfunction "K_2") (pintype "passive"))
      (node (ref "R184") (pin "2") (pinfunction "2_2") (pintype "passive"))
    )
    (net (code "70") (name "Net-(DS101-K)") (class "Default")
      (node (ref "DS101") (pin "2") (pinfunction "K_2") (pintype "passive"))
      (node (ref "DS102") (pin "1") (pinfunction "A_1") (pintype "passive"))
    )
    (net (code "71") (name "Net-(DS102-K)") (class "Default")
      (node (ref "DS102") (pin "2") (pinfunction "K_2") (pintype "passive"))
      (node (ref "R185") (pin "2") (pinfunction "2_2") (pintype "passive"))
    )
    (net (code "72") (name "Net-(DS109-K)") (class "Default")
      (node (ref "DS109") (pin "2") (pinfunction "K_2") (pintype "passive"))
      (node (ref "DS110") (pin "1") (pinfunction "A_1") (pintype "passive"))
    )
    (net (code "73") (name "Net-(DS110-K)") (class "Default")
      (node (ref "DS110") (pin "2") (pinfunction "K_2") (pintype "passive"))
      (node (ref "R189") (pin "2") (pinfunction "2_2") (pintype "passive"))
    )
    (net (code "74") (name "Net-(DS111-K)") (class "Default")
      (node (ref "DS111") (pin "2") (pinfunction "K_2") (pintype "passive"))
      (node (ref "DS112") (pin "1") (pinfunction "A_1") (pintype "passive"))
    )
    (net (code "75") (name "Net-(DS112-K)") (class "Default")
      (node (ref "DS112") (pin "2") (pinfunction "K_2") (pintype "passive"))
      (node (ref "R190") (pin "2") (pinfunction "2_2") (pintype "passive"))
    )
    (net (code "76") (name "Net-(DS113-K)") (class "Default")
      (node (ref "DS113") (pin "2") (pinfunction "K_2") (pintype "passive"))
      (node (ref "DS114") (pin "1") (pinfunction "A_1") (pintype "passive"))
    )
    (net (code "77") (name "Net-(DS114-K)") (class "Default")
      (node (ref "DS114") (pin "2") (pinfunction "K_2") (pintype "passive"))
      (node (ref "R191") (pin "2") (pinfunction "2_2") (pintype "passive"))
    )
    (net (code "78") (name "Net-(DS121-K)") (class "Default")
      (node (ref "DS121") (pin "2") (pinfunction "K_2") (pintype "passive"))
      (node (ref "DS122") (pin "1") (pinfunction "A_1") (pintype "passive"))
    )
    (net (code "79") (name "Net-(DS122-K)") (class "Default")
      (node (ref "DS122") (pin "2") (pinfunction "K_2") (pintype "passive"))
      (node (ref "R201") (pin "2") (pinfunction "2_2") (pintype "passive"))
    )
    (net (code "80") (name "Net-(DS123-K)") (class "Default")
      (node (ref "DS123") (pin "2") (pinfunction "K_2") (pintype "passive"))
      (node (ref "DS124") (pin "1") (pinfunction "A_1") (pintype "passive"))
    )
    (net (code "81") (name "Net-(DS124-K)") (class "Default")
      (node (ref "DS124") (pin "2") (pinfunction "K_2") (pintype "passive"))
      (node (ref "R202") (pin "2") (pinfunction "2_2") (pintype "passive"))
    )
    (net (code "82") (name "Net-(DS125-K)") (class "Default")
      (node (ref "DS125") (pin "2") (pinfunction "K_2") (pintype "passive"))
      (node (ref "DS126") (pin "1") (pinfunction "A_1") (pintype "passive"))
    )
    (net (code "83") (name "Net-(DS126-K)") (class "Default")
      (node (ref "DS126") (pin "2") (pinfunction "K_2") (pintype "passive"))
      (node (ref "R203") (pin "2") (pinfunction "2_2") (pintype "passive"))
    )
    (net (code "84") (name "Net-(DS133-K)") (class "Default")
      (node (ref "DS133") (pin "2") (pinfunction "K_2") (pintype "passive"))
      (node (ref "DS134") (pin "1") (pinfunction "A_1") (pintype "passive"))
    )
    (net (code "85") (name "Net-(DS134-K)") (class "Default")
      (node (ref "DS134") (pin "2") (pinfunction "K_2") (pintype "passive"))
      (node (ref "R207") (pin "2") (pinfunction "2_2") (pintype "passive"))
    )
    (net (code "86") (name "Net-(DS135-K)") (class "Default")
      (node (ref "DS135") (pin "2") (pinfunction "K_2") (pintype "passive"))
      (node (ref "DS136") (pin "1") (pinfunction "A_1") (pintype "passive"))
    )
    (net (code "87") (name "Net-(DS136-K)") (class "Default")
      (node (ref "DS136") (pin "2") (pinfunction "K_2") (pintype "passive"))
      (node (ref "R208") (pin "2") (pinfunction "2_2") (pintype "passive"))
    )
    (net (code "88") (name "Net-(DS137-K)") (class "Default")
      (node (ref "DS137") (pin "2") (pinfunction "K_2") (pintype "passive"))
      (node (ref "DS138") (pin "1") (pinfunction "A_1") (pintype "passive"))
    )
    (net (code "89") (name "Net-(DS138-K)") (class "Default")
      (node (ref "DS138") (pin "2") (pinfunction "K_2") (pintype "passive"))
      (node (ref "R209") (pin "2") (pinfunction "2_2") (pintype "passive"))
    )
    (net (code "90") (name "Net-(DS145-K)") (class "Default")
      (node (ref "DS145") (pin "2") (pinfunction "K_2") (pintype "passive"))
      (node (ref "DS146") (pin "1") (pinfunction "A_1") (pintype "passive"))
    )
    (net (code "91") (name "Net-(DS146-K)") (class "Default")
      (node (ref "DS146") (pin "2") (pinfunction "K_2") (pintype "passive"))
      (node (ref "R219") (pin "2") (pinfunction "2_2") (pintype "passive"))
    )
    (net (code "92") (name "Net-(DS147-K)") (class "Default")
      (node (ref "DS147") (pin "2") (pinfunction "K_2") (pintype "passive"))
      (node (ref "DS148") (pin "1") (pinfunction "A_1") (pintype "passive"))
    )
    (net (code "93") (name "Net-(DS148-K)") (class "Default")
      (node (ref "DS148") (pin "2") (pinfunction "K_2") (pintype "passive"))
      (node (ref "R220") (pin "2") (pinfunction "2_2") (pintype "passive"))
    )
    (net (code "94") (name "Net-(DS149-K)") (class "Default")
      (node (ref "DS149") (pin "2") (pinfunction "K_2") (pintype "passive"))
      (node (ref "DS150") (pin "1") (pinfunction "A_1") (pintype "passive"))
    )
    (net (code "95") (name "Net-(DS150-K)") (class "Default")
      (node (ref "DS150") (pin "2") (pinfunction "K_2") (pintype "passive"))
      (node (ref "R221") (pin "2") (pinfunction "2_2") (pintype "passive"))
    )
    (net (code "96") (name "Net-(DS157-K)") (class "Default")
      (node (ref "DS157") (pin "2") (pinfunction "K_2") (pintype "passive"))
      (node (ref "DS158") (pin "1") (pinfunction "A_1") (pintype "passive"))
    )
    (net (code "97") (name "Net-(DS158-K)") (class "Default")
      (node (ref "DS158") (pin "2") (pinfunction "K_2") (pintype "passive"))
      (node (ref "R225") (pin "2") (pinfunction "2_2") (pintype "passive"))
    )
    (net (code "98") (name "Net-(DS159-K)") (class "Default")
      (node (ref "DS159") (pin "2") (pinfunction "K_2") (pintype "passive"))
      (node (ref "DS160") (pin "1") (pinfunction "A_1") (pintype "passive"))
    )
    (net (code "99") (name "Net-(DS160-K)") (class "Default")
      (node (ref "DS160") (pin "2") (pinfunction "K_2") (pintype "passive"))
      (node (ref "R226") (pin "2") (pinfunction "2_2") (pintype "passive"))
    )
    (net (code "100") (name "Net-(DS161-K)") (class "Default")
      (node (ref "DS161") (pin "2") (pinfunction "K_2") (pintype "passive"))
      (node (ref "DS162") (pin "1") (pinfunction "A_1") (pintype "passive"))
    )
    (net (code "101") (name "Net-(DS162-K)") (class "Default")
      (node (ref "DS162") (pin "2") (pinfunction "K_2") (pintype "passive"))
      (node (ref "R227") (pin "2") (pinfunction "2_2") (pintype "passive"))
    )
    (net (code "102") (name "Net-(Q22-B)") (class "Default")
      (node (ref "Q22") (pin "1") (pinfunction "B_1") (pintype "passive"))
      (node (ref "R105") (pin "2") (pinfunction "2_2") (pintype "passive"))
    )
    (net (code "103") (name "Net-(Q22-C)") (class "Default")
      (node (ref "Q22") (pin "3") (pinfunction "C_3") (pintype "passive"))
      (node (ref "R111") (pin "1") (pinfunction "1_1") (pintype "passive"))
      (node (ref "R117") (pin "1") (pinfunction "1_1") (pintype "passive"))
    )
    (net (code "104") (name "Net-(Q23-B)") (class "Default")
      (node (ref "Q23") (pin "1") (pinfunction "B_1") (pintype "passive"))
      (node (ref "R106") (pin "2") (pinfunction "2_2") (pintype "passive"))
    )
    (net (code "105") (name "Net-(Q23-C)") (class "Default")
      (node (ref "Q23") (pin "3") (pinfunction "C_3") (pintype "passive"))
      (node (ref "R112") (pin "1") (pinfunction "1_1") (pintype "passive"))
      (node (ref "R118") (pin "1") (pinfunction "1_1") (pintype "passive"))
    )
    (net (code "106") (name "Net-(Q24-B)") (class "Default")
      (node (ref "Q24") (pin "1") (pinfunction "B_1") (pintype "passive"))
      (node (ref "R107") (pin "2") (pinfunction "2_2") (pintype "passive"))
    )
    (net (code "107") (name "Net-(Q24-C)") (class "Default")
      (node (ref "Q24") (pin "3") (pinfunction "C_3") (pintype "passive"))
      (node (ref "R113") (pin "1") (pinfunction "1_1") (pintype "passive"))
      (node (ref "R119") (pin "1") (pinfunction "1_1") (pintype "passive"))
    )
    (net (code "108") (name "Net-(Q28-B)") (class "Default")
      (node (ref "Q28") (pin "1") (pinfunction "B_1") (pintype "passive"))
      (node (ref "R123") (pin "2") (pinfunction "2_2") (pintype "passive"))
    )
    (net (code "109") (name "Net-(Q28-C)") (class "Default")
      (node (ref "Q28") (pin "3") (pinfunction "C_3") (pintype "passive"))
      (node (ref "R129") (pin "1") (pinfunction "1_1") (pintype "passive"))
      (node (ref "R135") (pin "1") (pinfunction "1_1") (pintype "passive"))
    )
    (net (code "110") (name "Net-(Q29-B)") (class "Default")
      (node (ref "Q29") (pin "1") (pinfunction "B_1") (pintype "passive"))
      (node (ref "R124") (pin "2") (pinfunction "2_2") (pintype "passive"))
    )
    (net (code "111") (name "Net-(Q29-C)") (class "Default")
      (node (ref "Q29") (pin "3") (pinfunction "C_3") (pintype "passive"))
      (node (ref "R130") (pin "1") (pinfunction "1_1") (pintype "passive"))
      (node (ref "R136") (pin "1") (pinfunction "1_1") (pintype "passive"))
    )
    (net (code "112") (name "Net-(Q30-B)") (class "Default")
      (node (ref "Q30") (pin "1") (pinfunction "B_1") (pintype "passive"))
      (node (ref "R125") (pin "2") (pinfunction "2_2") (pintype "passive"))
    )
    (net (code "113") (name "Net-(Q30-C)") (class "Default")
      (node (ref "Q30") (pin "3") (pinfunction "C_3") (pintype "passive"))
      (node (ref "R131") (pin "1") (pinfunction "1_1") (pintype "passive"))
      (node (ref "R137") (pin "1") (pinfunction "1_1") (pintype "passive"))
    )
    (net (code "114") (name "Net-(Q34-B)") (class "Default")
      (node (ref "Q34") (pin "1") (pinfunction "B_1") (pintype "passive"))
      (node (ref "R141") (pin "2") (pinfunction "2_2") (pintype "passive"))
    )
    (net (code "115") (name "Net-(Q34-C)") (class "Default")
      (node (ref "Q34") (pin "3") (pinfunction "C_3") (pintype "passive"))
      (node (ref "R147") (pin "1") (pinfunction "1_1") (pintype "passive"))
      (node (ref "R153") (pin "1") (pinfunction "1_1") (pintype "passive"))
    )
    (net (code "116") (name "Net-(Q35-B)") (class "Default")
      (node (ref "Q35") (pin "1") (pinfunction "B_1") (pintype "passive"))
      (node (ref "R142") (pin "2") (pinfunction "2_2") (pintype "passive"))
    )
    (net (code "117") (name "Net-(Q35-C)") (class "Default")
      (node (ref "Q35") (pin "3") (pinfunction "C_3") (pintype "passive"))
      (node (ref "R148") (pin "1") (pinfunction "1_1") (pintype "passive"))
      (node (ref "R154") (pin "1") (pinfunction "1_1") (pintype "passive"))
    )
    (net (code "118") (name "Net-(Q36-B)") (class "Default")
      (node (ref "Q36") (pin "1") (pinfunction "B_1") (pintype "passive"))
      (node (ref "R143") (pin "2") (pinfunction "2_2") (pintype "passive"))
    )
    (net (code "119") (name "Net-(Q36-C)") (class "Default")
      (node (ref "Q36") (pin "3") (pinfunction "C_3") (pintype "passive"))
      (node (ref "R149") (pin "1") (pinfunction "1_1") (pintype "passive"))
      (node (ref "R155") (pin "1") (pinfunction "1_1") (pintype "passive"))
    )
    (net (code "120") (name "Net-(Q40-B)") (class "Default")
      (node (ref "Q40") (pin "1") (pinfunction "B_1") (pintype "passive"))
      (node (ref "R159") (pin "2") (pinfunction "2_2") (pintype "passive"))
    )
    (net (code "121") (name "Net-(Q40-C)") (class "Default")
      (node (ref "Q40") (pin "3") (pinfunction "C_3") (pintype "passive"))
      (node (ref "R165") (pin "1") (pinfunction "1_1") (pintype "passive"))
      (node (ref "R171") (pin "1") (pinfunction "1_1") (pintype "passive"))
    )
    (net (code "122") (name "Net-(Q41-B)") (class "Default")
      (node (ref "Q41") (pin "1") (pinfunction "B_1") (pintype "passive"))
      (node (ref "R160") (pin "2") (pinfunction "2_2") (pintype "passive"))
    )
    (net (code "123") (name "Net-(Q41-C)") (class "Default")
      (node (ref "Q41") (pin "3") (pinfunction "C_3") (pintype "passive"))
      (node (ref "R166") (pin "1") (pinfunction "1_1") (pintype "passive"))
      (node (ref "R172") (pin "1") (pinfunction "1_1") (pintype "passive"))
    )
    (net (code "124") (name "Net-(Q42-B)") (class "Default")
      (node (ref "Q42") (pin "1") (pinfunction "B_1") (pintype "passive"))
      (node (ref "R161") (pin "2") (pinfunction "2_2") (pintype "passive"))
    )
    (net (code "125") (name "Net-(Q42-C)") (class "Default")
      (node (ref "Q42") (pin "3") (pinfunction "C_3") (pintype "passive"))
      (node (ref "R167") (pin "1") (pinfunction "1_1") (pintype "passive"))
      (node (ref "R173") (pin "1") (pinfunction "1_1") (pintype "passive"))
    )
    (net (code "126") (name "Net-(Q46-B)") (class "Default")
      (node (ref "Q46") (pin "1") (pinfunction "B_1") (pintype "passive"))
      (node (ref "R177") (pin "2") (pinfunction "2_2") (pintype "passive"))
    )
    (net (code "127") (name "Net-(Q46-C)") (class "Default")
      (node (ref "Q46") (pin "3") (pinfunction "C_3") (pintype "passive"))
      (node (ref "R183") (pin "1") (pinfunction "1_1") (pintype "passive"))
      (node (ref "R189") (pin "1") (pinfunction "1_1") (pintype "passive"))
    )
    (net (code "128") (name "Net-(Q47-B)") (class "Default")
      (node (ref "Q47") (pin "1") (pinfunction "B_1") (pintype "passive"))
      (node (ref "R178") (pin "2") (pinfunction "2_2") (pintype "passive"))
    )
    (net (code "129") (name "Net-(Q47-C)") (class "Default")
      (node (ref "Q47") (pin "3") (pinfunction "C_3") (pintype "passive"))
      (node (ref "R184") (pin "1") (pinfunction "1_1") (pintype "passive"))
      (node (ref "R190") (pin "1") (pinfunction "1_1") (pintype "passive"))
    )
    (net (code "130") (name "Net-(Q48-B)") (class "Default")
      (node (ref "Q48") (pin "1") (pinfunction "B_1") (pintype "passive"))
      (node (ref "R179") (pin "2") (pinfunction "2_2") (pintype "passive"))
    )
    (net (code "131") (name "Net-(Q48-C)") (class "Default")
      (node (ref "Q48") (pin "3") (pinfunction "C_3") (pintype "passive"))
      (node (ref "R185") (pin "1") (pinfunction "1_1") (pintype "passive"))
      (node (ref "R191") (pin "1") (pinfunction "1_1") (pintype "passive"))
    )
    (net (code "132") (name "Net-(Q52-B)") (class "Default")
      (node (ref "Q52") (pin "1") (pinfunction "B_1") (pintype "passive"))
      (node (ref "R195") (pin "2") (pinfunction "2_2") (pintype "passive"))
    )
    (net (code "133") (name "Net-(Q52-C)") (class "Default")
      (node (ref "Q52") (pin "3") (pinfunction "C_3") (pintype "passive"))
      (node (ref "R201") (pin "1") (pinfunction "1_1") (pintype "passive"))
      (node (ref "R207") (pin "1") (pinfunction "1_1") (pintype "passive"))
    )
    (net (code "134") (name "Net-(Q53-B)") (class "Default")
      (node (ref "Q53") (pin "1") (pinfunction "B_1") (pintype "passive"))
      (node (ref "R196") (pin "2") (pinfunction "2_2") (pintype "passive"))
    )
    (net (code "135") (name "Net-(Q53-C)") (class "Default")
      (node (ref "Q53") (pin "3") (pinfunction "C_3") (pintype "passive"))
      (node (ref "R202") (pin "1") (pinfunction "1_1") (pintype "passive"))
      (node (ref "R208") (pin "1") (pinfunction "1_1") (pintype "passive"))
    )
    (net (code "136") (name "Net-(Q54-B)") (class "Default")
      (node (ref "Q54") (pin "1") (pinfunction "B_1") (pintype "passive"))
      (node (ref "R197") (pin "2") (pinfunction "2_2") (pintype "passive"))
    )
    (net (code "137") (name "Net-(Q54-C)") (class "Default")
      (node (ref "Q54") (pin "3") (pinfunction "C_3") (pintype "passive"))
      (node (ref "R203") (pin "1") (pinfunction "1_1") (pintype "passive"))
      (node (ref "R209") (pin "1") (pinfunction "1_1") (pintype "passive"))
    )
    (net (code "138") (name "Net-(Q58-B)") (class "Default")
      (node (ref "Q58") (pin "1") (pinfunction "B_1") (pintype "passive"))
      (node (ref "R213") (pin "2") (pinfunction "2_2") (pintype "passive"))
    )
    (net (code "139") (name "Net-(Q58-C)") (class "Default")
      (node (ref "Q58") (pin "3") (pinfunction "C_3") (pintype "passive"))
      (node (ref "R219") (pin "1") (pinfunction "1_1") (pintype "passive"))
      (node (ref "R225") (pin "1") (pinfunction "1_1") (pintype "passive"))
    )
    (net (code "140") (name "Net-(Q59-B)") (class "Default")
      (node (ref "Q59") (pin "1") (pinfunction "B_1") (pintype "passive"))
      (node (ref "R214") (pin "2") (pinfunction "2_2") (pintype "passive"))
    )
    (net (code "141") (name "Net-(Q59-C)") (class "Default")
      (node (ref "Q59") (pin "3") (pinfunction "C_3") (pintype "passive"))
      (node (ref "R220") (pin "1") (pinfunction "1_1") (pintype "passive"))
      (node (ref "R226") (pin "1") (pinfunction "1_1") (pintype "passive"))
    )
    (net (code "142") (name "Net-(Q60-B)") (class "Default")
      (node (ref "Q60") (pin "1") (pinfunction "B_1") (pintype "passive"))
      (node (ref "R215") (pin "2") (pinfunction "2_2") (pintype "passive"))
    )
    (net (code "143") (name "Net-(Q60-C)") (class "Default")
      (node (ref "Q60") (pin "3") (pinfunction "C_3") (pintype "passive"))
      (node (ref "R221") (pin "1") (pinfunction "1_1") (pintype "passive"))
      (node (ref "R227") (pin "1") (pinfunction "1_1") (pintype "passive"))
    )
    (net (code "144") (name "Net-(U19-Q1)") (class "Default")
      (node (ref "R105") (pin "1") (pinfunction "1_1") (pintype "passive"))
      (node (ref "U19") (pin "19") (pinfunction "Q1_19") (pintype "tri_state"))
    )
    (net (code "145") (name "Net-(U19-Q2)") (class "Default")
      (node (ref "R123") (pin "1") (pinfunction "1_1") (pintype "passive"))
      (node (ref "U19") (pin "18") (pinfunction "Q2_18") (pintype "tri_state"))
    )
    (net (code "146") (name "Net-(U19-Q3)") (class "Default")
      (node (ref "R141") (pin "1") (pinfunction "1_1") (pintype "passive"))
      (node (ref "U19") (pin "17") (pinfunction "Q3_17") (pintype "tri_state"))
    )
    (net (code "147") (name "Net-(U19-Q4)") (class "Default")
      (node (ref "R159") (pin "1") (pinfunction "1_1") (pintype "passive"))
      (node (ref "U19") (pin "16") (pinfunction "Q4_16") (pintype "tri_state"))
    )
    (net (code "148") (name "Net-(U19-Q5)") (class "Default")
      (node (ref "R177") (pin "1") (pinfunction "1_1") (pintype "passive"))
      (node (ref "U19") (pin "15") (pinfunction "Q5_15") (pintype "tri_state"))
    )
    (net (code "149") (name "Net-(U19-Q6)") (class "Default")
      (node (ref "R195") (pin "1") (pinfunction "1_1") (pintype "passive"))
      (node (ref "U19") (pin "14") (pinfunction "Q6_14") (pintype "tri_state"))
    )
    (net (code "150") (name "Net-(U19-Q7)") (class "Default")
      (node (ref "R213") (pin "1") (pinfunction "1_1") (pintype "passive"))
      (node (ref "U19") (pin "13") (pinfunction "Q7_13") (pintype "tri_state"))
    )
    (net (code "151") (name "Net-(U20-Q1)") (class "Default")
      (node (ref "R106") (pin "1") (pinfunction "1_1") (pintype "passive"))
      (node (ref "U20") (pin "19") (pinfunction "Q1_19") (pintype "tri_state"))
    )
    (net (code "152") (name "Net-(U20-Q2)") (class "Default")
      (node (ref "R124") (pin "1") (pinfunction "1_1") (pintype "passive"))
      (node (ref "U20") (pin "18") (pinfunction "Q2_18") (pintype "tri_state"))
    )
    (net (code "153") (name "Net-(U20-Q3)") (class "Default")
      (node (ref "R142") (pin "1") (pinfunction "1_1") (pintype "passive"))
      (node (ref "U20") (pin "17") (pinfunction "Q3_17") (pintype "tri_state"))
    )
    (net (code "154") (name "Net-(U20-Q4)") (class "Default")
      (node (ref "R160") (pin "1") (pinfunction "1_1") (pintype "passive"))
      (node (ref "U20") (pin "16") (pinfunction "Q4_16") (pintype "tri_state"))
    )
    (net (code "155") (name "Net-(U20-Q5)") (class "Default")
      (node (ref "R178") (pin "1") (pinfunction "1_1") (pintype "passive"))
      (node (ref "U20") (pin "15") (pinfunction "Q5_15") (pintype "tri_state"))
    )
    (net (code "156") (name "Net-(U20-Q6)") (class "Default")
      (node (ref "R196") (pin "1") (pinfunction "1_1") (pintype "passive"))
      (node (ref "U20") (pin "14") (pinfunction "Q6_14") (pintype "tri_state"))
    )
    (net (code "157") (name "Net-(U20-Q7)") (class "Default")
      (node (ref "R214") (pin "1") (pinfunction "1_1") (pintype "passive"))
      (node (ref "U20") (pin "13") (pinfunction "Q7_13") (pintype "tri_state"))
    )
    (net (code "158") (name "Net-(U21-Q1)") (class "Default")
      (node (ref "R107") (pin "1") (pinfunction "1_1") (pintype "passive"))
      (node (ref "U21") (pin "19") (pinfunction "Q1_19") (pintype "tri_state"))
    )
    (net (code "159") (name "Net-(U21-Q2)") (class "Default")
      (node (ref "R125") (pin "1") (pinfunction "1_1") (pintype "passive"))
      (node (ref "U21") (pin "18") (pinfunction "Q2_18") (pintype "tri_state"))
    )
    (net (code "160") (name "Net-(U21-Q3)") (class "Default")
      (node (ref "R143") (pin "1") (pinfunction "1_1") (pintype "passive"))
      (node (ref "U21") (pin "17") (pinfunction "Q3_17") (pintype "tri_state"))
    )
    (net (code "161") (name "Net-(U21-Q4)") (class "Default")
      (node (ref "R161") (pin "1") (pinfunction "1_1") (pintype "passive"))
      (node (ref "U21") (pin "16") (pinfunction "Q4_16") (pintype "tri_state"))
    )
    (net (code "162") (name "Net-(U21-Q5)") (class "Default")
      (node (ref "R179") (pin "1") (pinfunction "1_1") (pintype "passive"))
      (node (ref "U21") (pin "15") (pinfunction "Q5_15") (pintype "tri_state"))
    )
    (net (code "163") (name "Net-(U21-Q6)") (class "Default")
      (node (ref "R197") (pin "1") (pinfunction "1_1") (pintype "passive"))
      (node (ref "U21") (pin "14") (pinfunction "Q6_14") (pintype "tri_state"))
    )
    (net (code "164") (name "Net-(U21-Q7)") (class "Default")
      (node (ref "R215") (pin "1") (pinfunction "1_1") (pintype "passive"))
      (node (ref "U21") (pin "13") (pinfunction "Q7_13") (pintype "tri_state"))
    )
    (net (code "165") (name "VCC") (class "Default")
      (node (ref "C47") (pin "1") (pinfunction "1_1") (pintype "passive"))
      (node (ref "C48") (pin "1") (pinfunction "1_1") (pintype "passive"))
      (node (ref "C49") (pin "1") (pinfunction "1_1") (pintype "passive"))
      (node (ref "U19") (pin "20") (pinfunction "VCC_20") (pintype "power_in"))
      (node (ref "U20") (pin "20") (pinfunction "VCC_20") (pintype "power_in"))
      (node (ref "U21") (pin "20") (pinfunction "VCC_20") (pintype "power_in"))
    )
  )
)
